# test-board-128-256.net
KiCad netlist of a schematic drawn in EAGLE
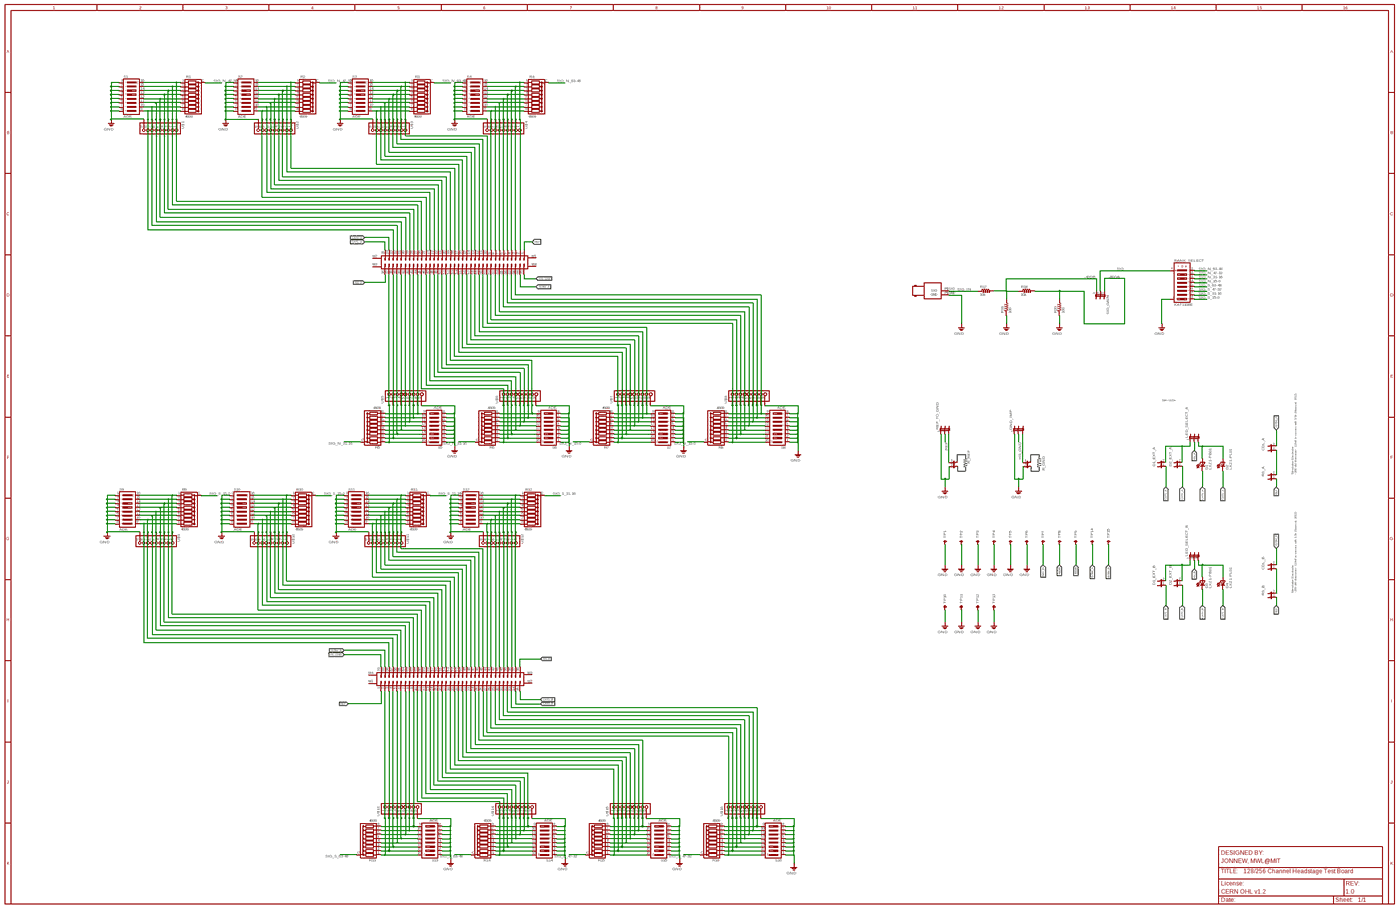
[diagram p0: schematic, sheet 1, overview]
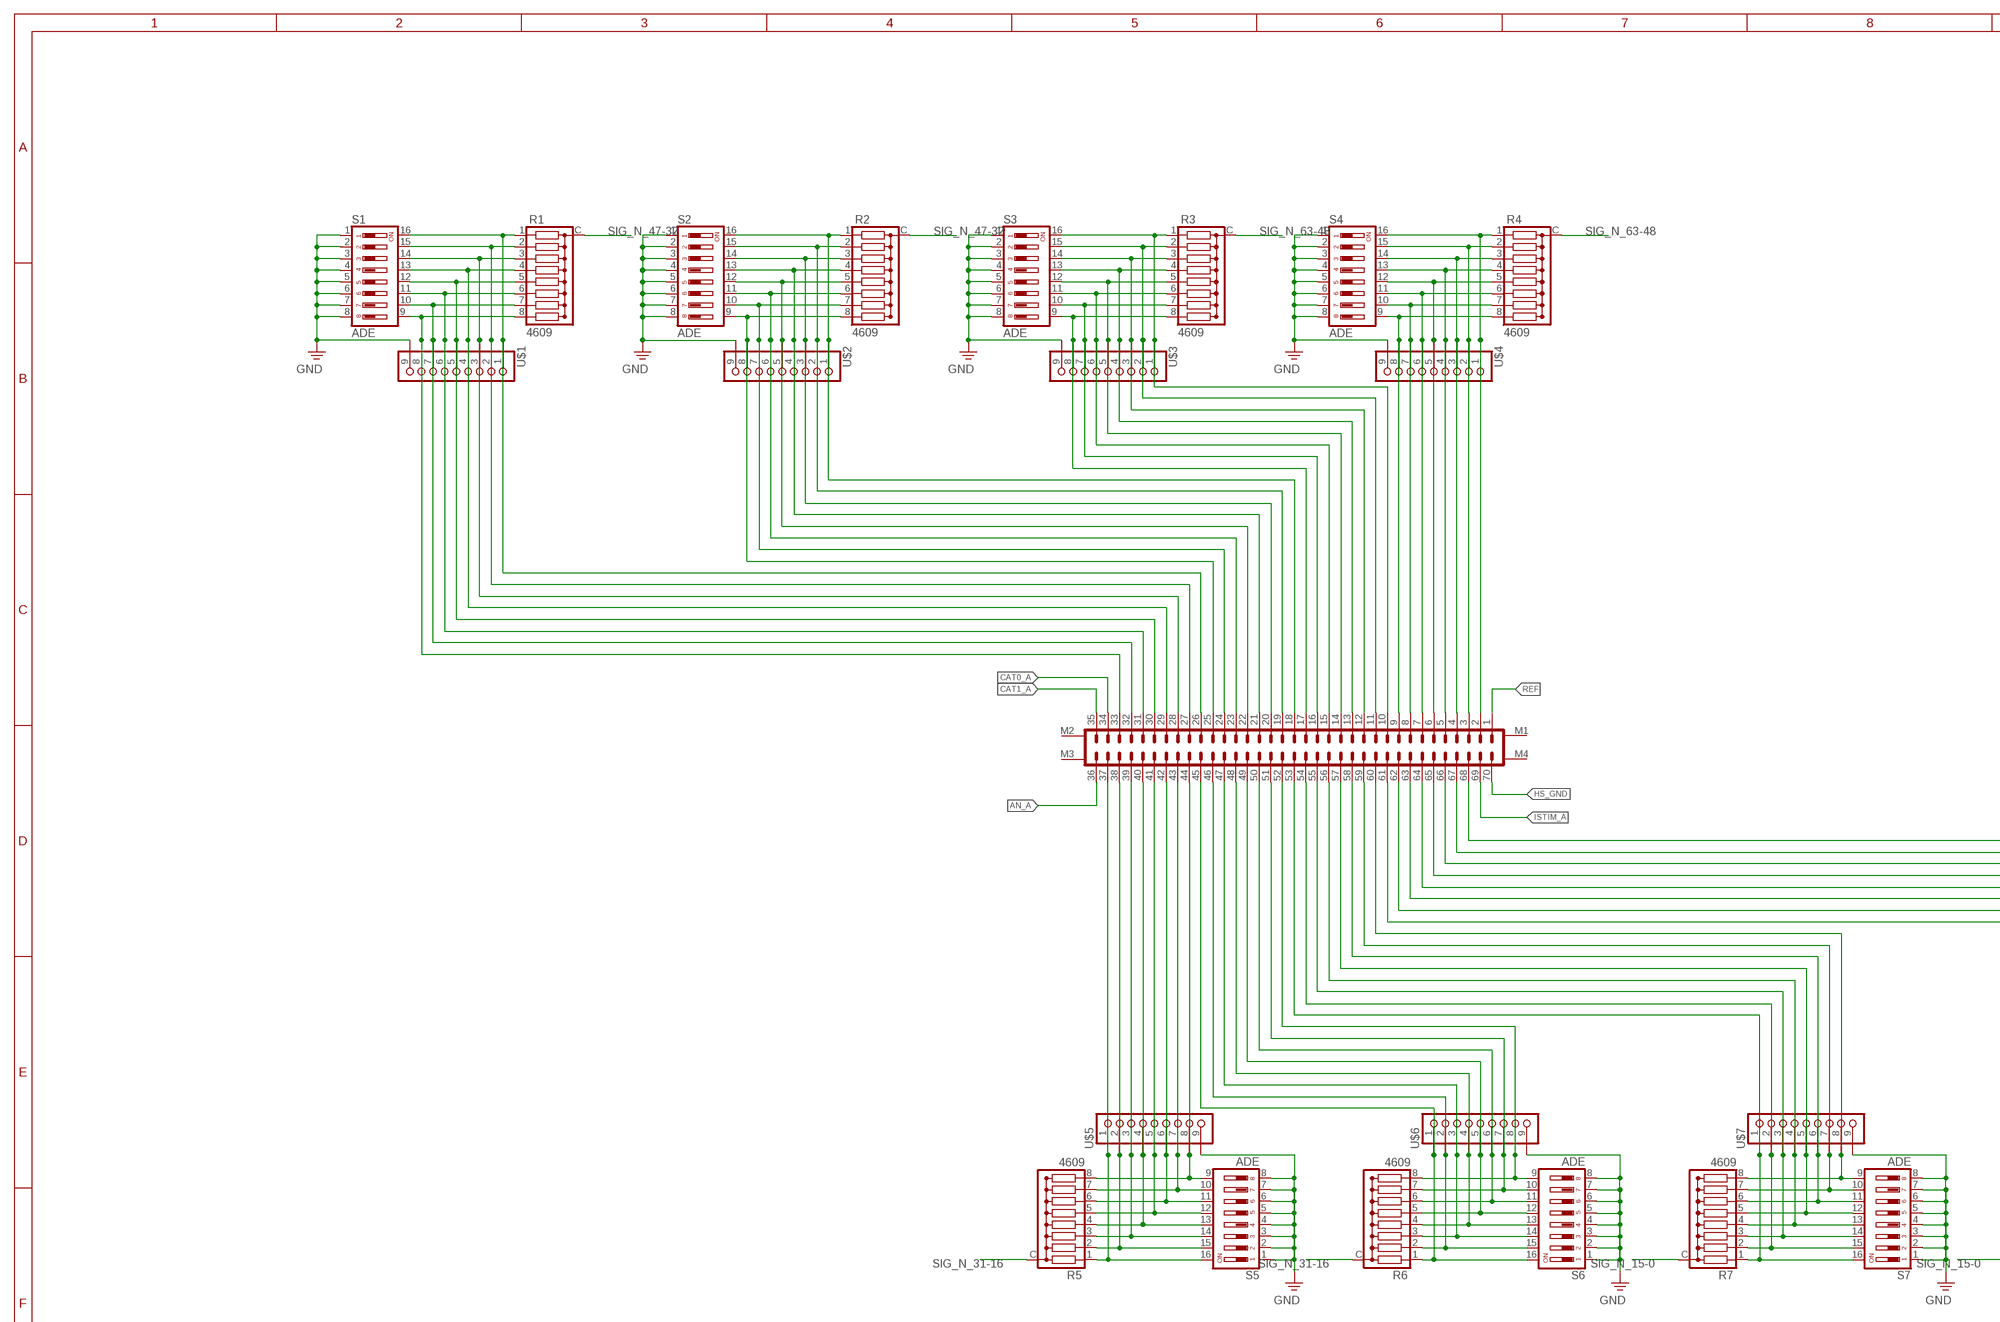
[diagram p1: schematic, sheet 1, part 1 of 4]
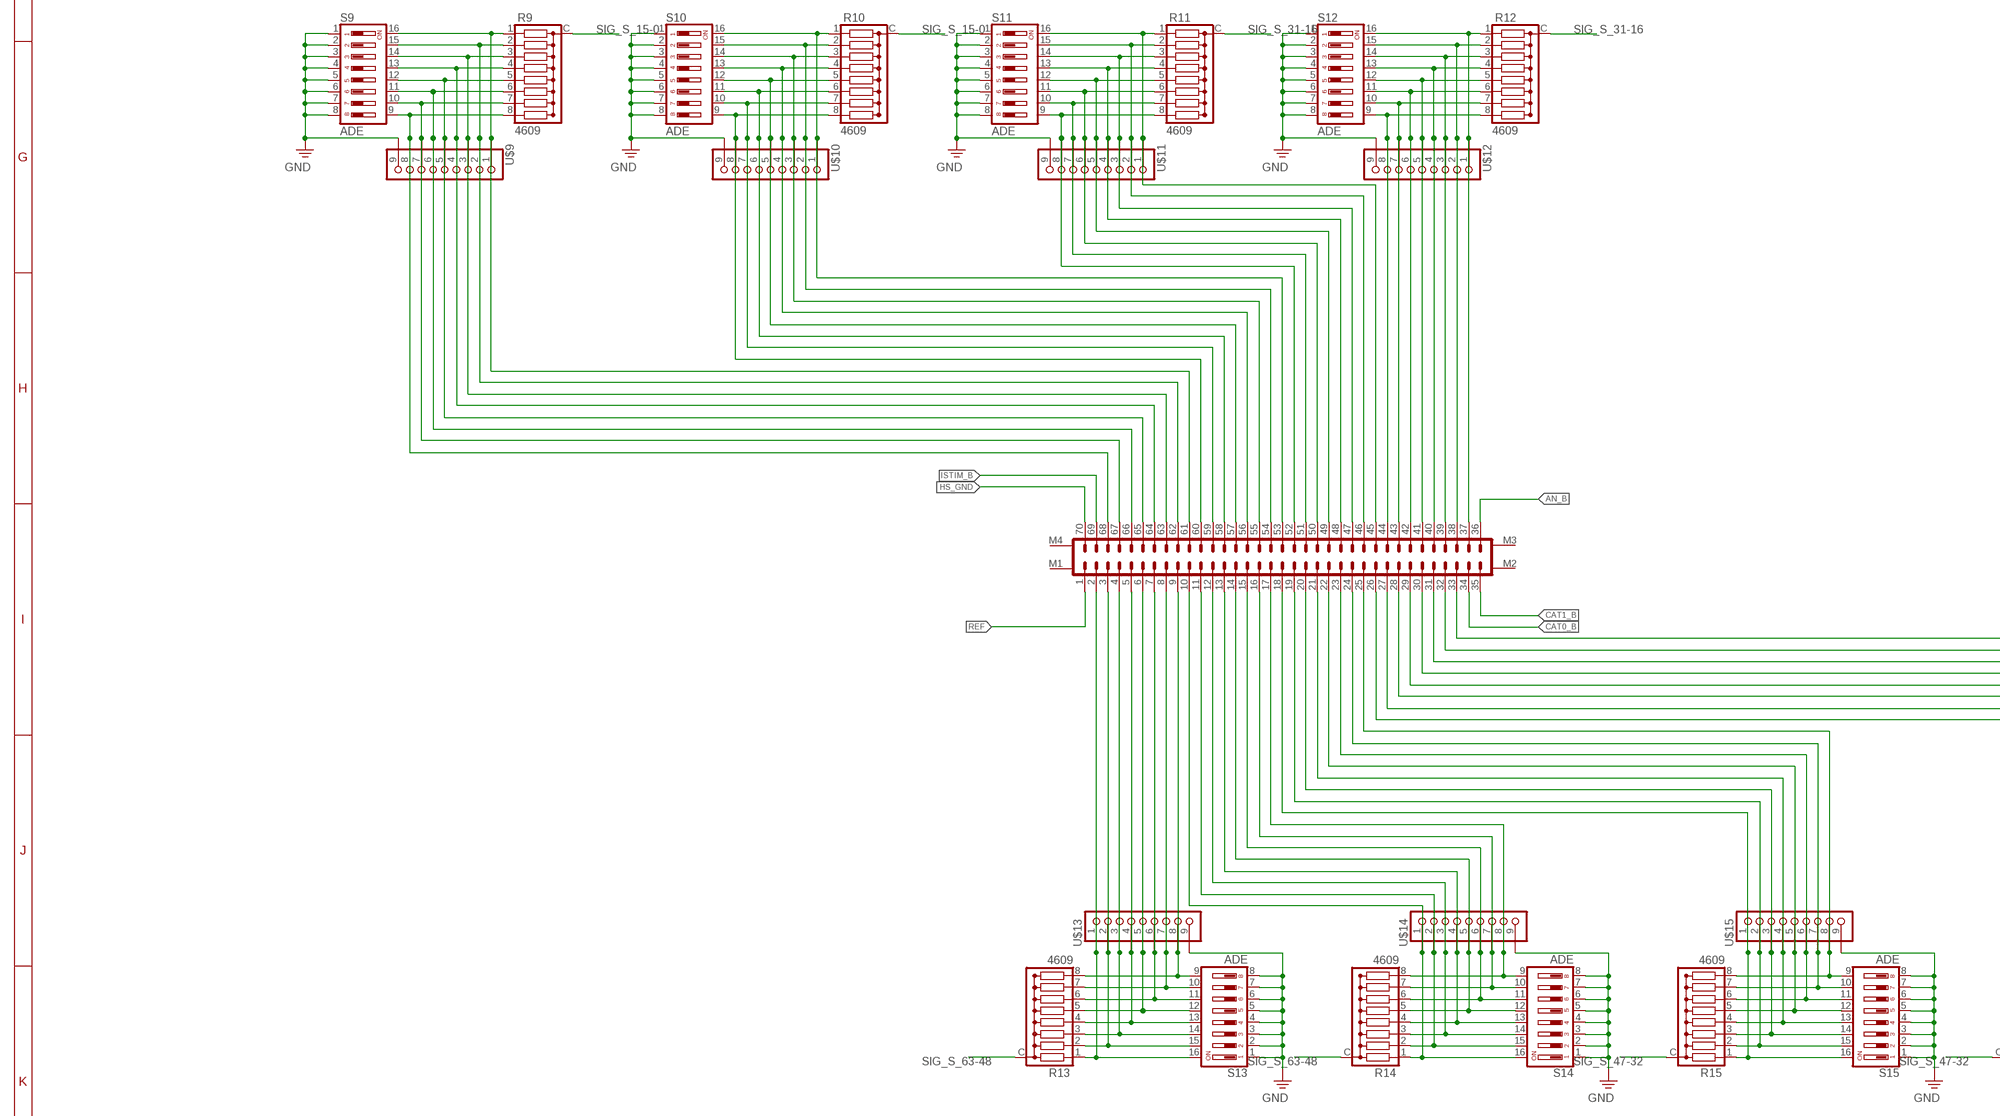
[diagram p2: schematic, sheet 1, part 2 of 4]
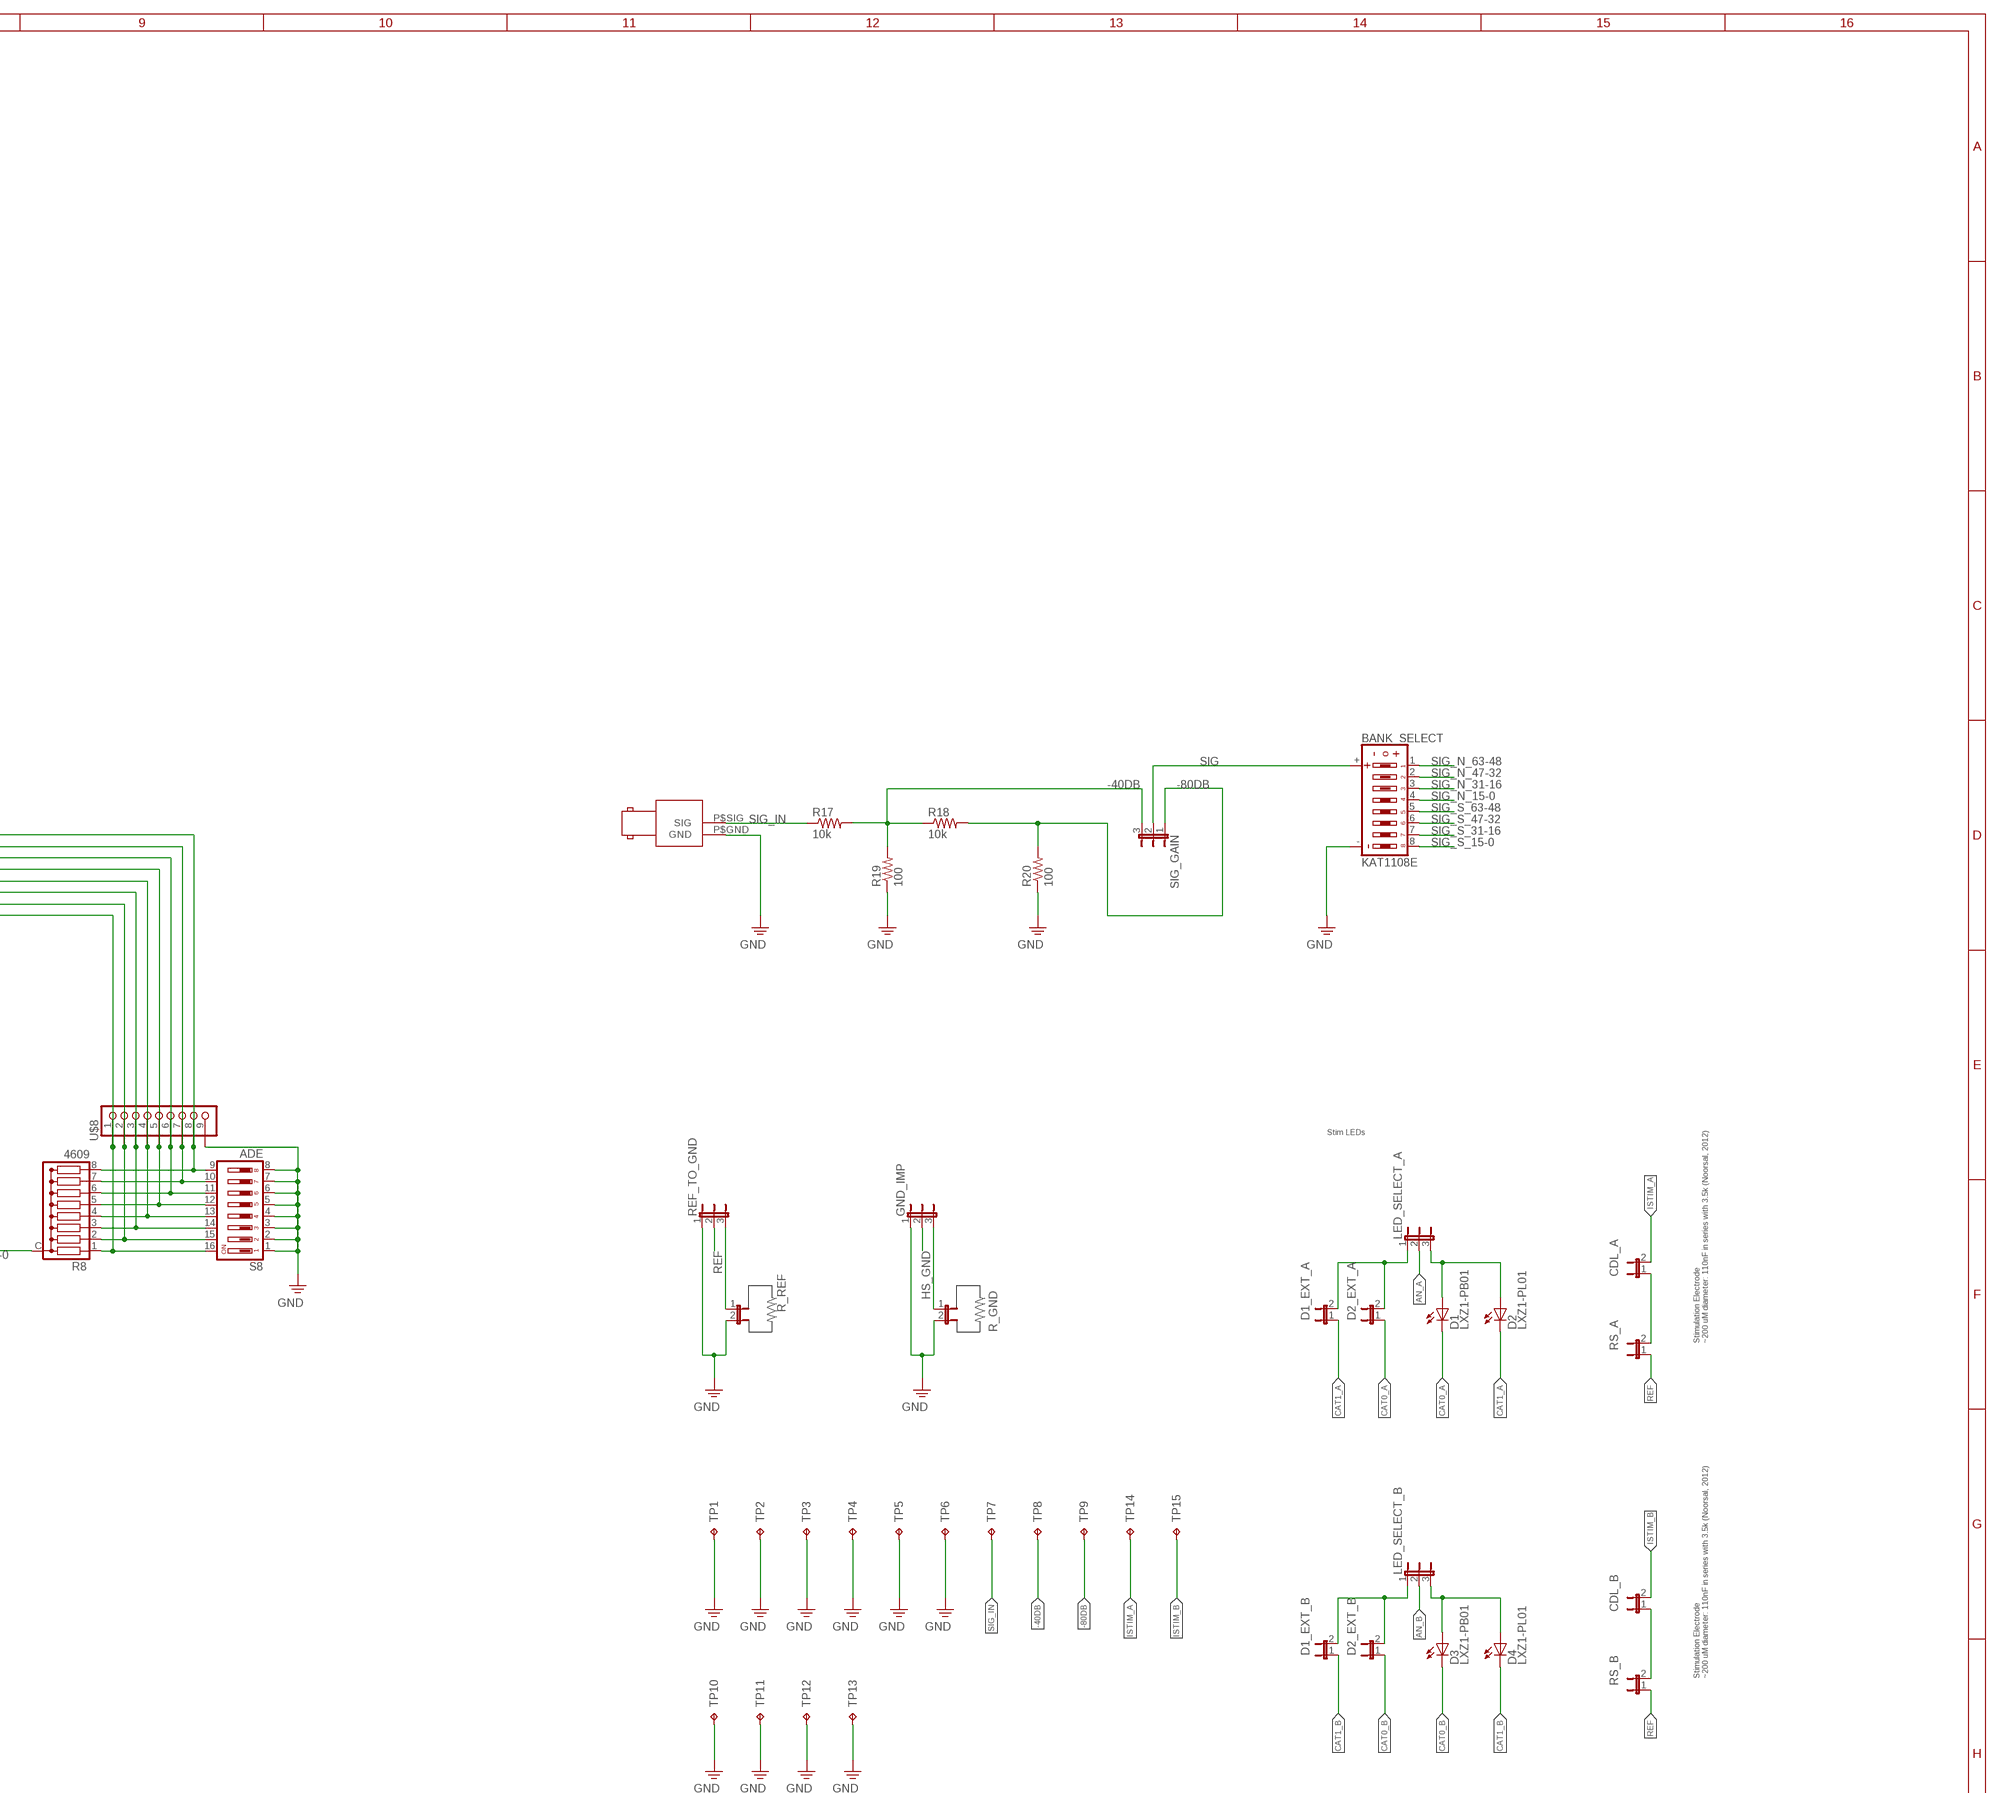
[diagram p3: schematic, sheet 1, part 3 of 4]
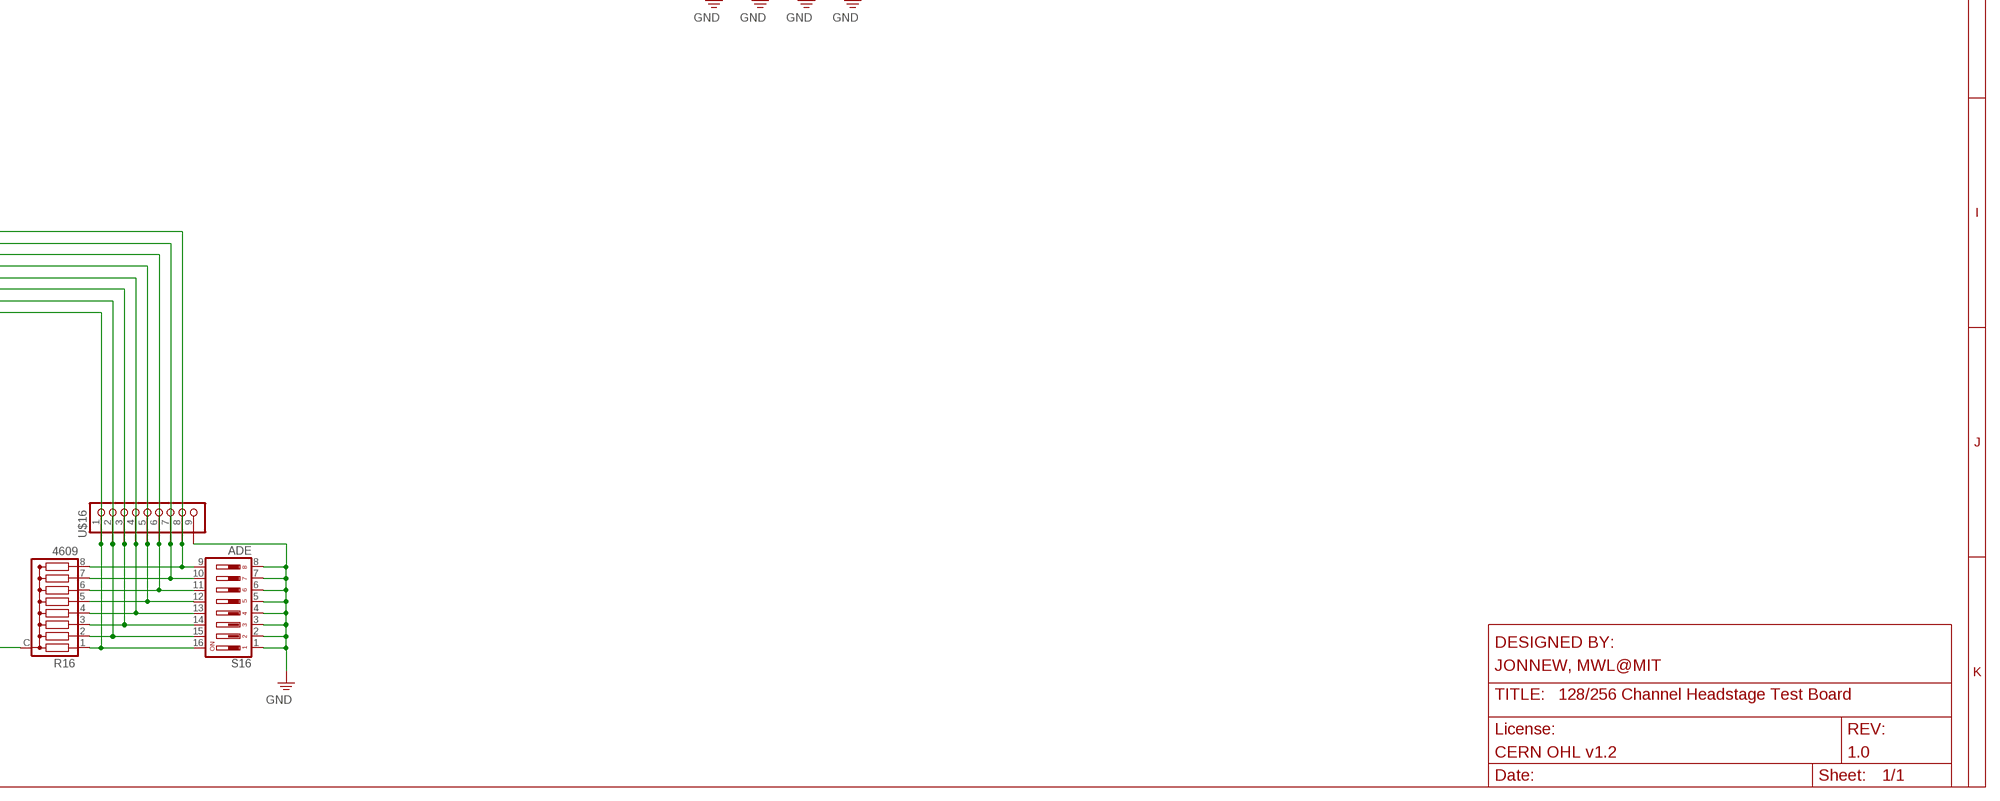
[diagram p4: schematic, sheet 1, part 4 of 4]

(export (version "E")
  (design (tool "Eeschema 10.0.6"))
  (components
    (comp (ref "A-OR-D")
      (value "DF40HEAD")
      (footprint "eagle-import:DF40-70HEAD")
      (libsource (lib "eagle-import") (part "PINHD-2X35+4_DF40-70HEAD"))
    )
    (comp (ref "B-OR-C")
      (value "DF40HEAD")
      (footprint "eagle-import:DF40-70HEAD")
      (libsource (lib "eagle-import") (part "PINHD-2X35+4_DF40-70HEAD"))
    )
    (comp (ref "BANK_SELECT")
      (value "KAT1108E")
      (footprint "eagle-import:206-124_DIP8-SPDT")
      (libsource (lib "eagle-import") (part "DIPSW-008-SPDT_206-124"))
    )
    (comp (ref "CDL_A")
      (value "JP2E_THRU-HOLE")
      (footprint "eagle-import:JP2")
      (libsource (lib "eagle-import") (part "JP2E_THRU-HOLE"))
    )
    (comp (ref "CDL_B")
      (value "JP2E_THRU-HOLE")
      (footprint "eagle-import:JP2")
      (libsource (lib "eagle-import") (part "JP2E_THRU-HOLE"))
    )
    (comp (ref "D1")
      (value "LXZ1-PB01")
      (footprint "eagle-import:LXZ1")
      (libsource (lib "eagle-import") (part "LED_LXZ1"))
    )
    (comp (ref "D1_EXT_A")
      (value "JP2E_THRU-HOLE")
      (footprint "eagle-import:JP2")
      (libsource (lib "eagle-import") (part "JP2E_THRU-HOLE"))
    )
    (comp (ref "D1_EXT_B")
      (value "JP2E_THRU-HOLE")
      (footprint "eagle-import:JP2")
      (libsource (lib "eagle-import") (part "JP2E_THRU-HOLE"))
    )
    (comp (ref "D2")
      (value "LXZ1-PL01")
      (footprint "eagle-import:LXZ1")
      (libsource (lib "eagle-import") (part "LED_LXZ1"))
    )
    (comp (ref "D2_EXT_A")
      (value "JP2E_THRU-HOLE")
      (footprint "eagle-import:JP2")
      (libsource (lib "eagle-import") (part "JP2E_THRU-HOLE"))
    )
    (comp (ref "D2_EXT_B")
      (value "JP2E_THRU-HOLE")
      (footprint "eagle-import:JP2")
      (libsource (lib "eagle-import") (part "JP2E_THRU-HOLE"))
    )
    (comp (ref "D3")
      (value "LXZ1-PB01")
      (footprint "eagle-import:LXZ1")
      (libsource (lib "eagle-import") (part "LED_LXZ1"))
    )
    (comp (ref "D4")
      (value "LXZ1-PL01")
      (footprint "eagle-import:LXZ1")
      (libsource (lib "eagle-import") (part "LED_LXZ1"))
    )
    (comp (ref "GND_IMP")
      (value "JP3E")
      (footprint "eagle-import:JP3")
      (libsource (lib "eagle-import") (part "JP3E"))
    )
    (comp (ref "LED_SELECT_A")
      (value "JP3E")
      (footprint "eagle-import:JP3")
      (libsource (lib "eagle-import") (part "JP3E"))
    )
    (comp (ref "LED_SELECT_B")
      (value "JP3E")
      (footprint "eagle-import:JP3")
      (libsource (lib "eagle-import") (part "JP3E"))
    )
    (comp (ref "R1")
      (value "4609")
      (footprint "eagle-import:RNX8-0.1")
      (libsource (lib "eagle-import") (part "RN1X8"))
    )
    (comp (ref "R2")
      (value "4609")
      (footprint "eagle-import:RNX8-0.1")
      (libsource (lib "eagle-import") (part "RN1X8"))
    )
    (comp (ref "R3")
      (value "4609")
      (footprint "eagle-import:RNX8-0.1")
      (libsource (lib "eagle-import") (part "RN1X8"))
    )
    (comp (ref "R4")
      (value "4609")
      (footprint "eagle-import:RNX8-0.1")
      (libsource (lib "eagle-import") (part "RN1X8"))
    )
    (comp (ref "R5")
      (value "4609")
      (footprint "eagle-import:RNX8-0.1")
      (libsource (lib "eagle-import") (part "RN1X8"))
    )
    (comp (ref "R6")
      (value "4609")
      (footprint "eagle-import:RNX8-0.1")
      (libsource (lib "eagle-import") (part "RN1X8"))
    )
    (comp (ref "R7")
      (value "4609")
      (footprint "eagle-import:RNX8-0.1")
      (libsource (lib "eagle-import") (part "RN1X8"))
    )
    (comp (ref "R8")
      (value "4609")
      (footprint "eagle-import:RNX8-0.1")
      (libsource (lib "eagle-import") (part "RN1X8"))
    )
    (comp (ref "R9")
      (value "4609")
      (footprint "eagle-import:RNX8-0.1")
      (libsource (lib "eagle-import") (part "RN1X8"))
    )
    (comp (ref "R10")
      (value "4609")
      (footprint "eagle-import:RNX8-0.1")
      (libsource (lib "eagle-import") (part "RN1X8"))
    )
    (comp (ref "R11")
      (value "4609")
      (footprint "eagle-import:RNX8-0.1")
      (libsource (lib "eagle-import") (part "RN1X8"))
    )
    (comp (ref "R12")
      (value "4609")
      (footprint "eagle-import:RNX8-0.1")
      (libsource (lib "eagle-import") (part "RN1X8"))
    )
    (comp (ref "R13")
      (value "4609")
      (footprint "eagle-import:RNX8-0.1")
      (libsource (lib "eagle-import") (part "RN1X8"))
    )
    (comp (ref "R14")
      (value "4609")
      (footprint "eagle-import:RNX8-0.1")
      (libsource (lib "eagle-import") (part "RN1X8"))
    )
    (comp (ref "R15")
      (value "4609")
      (footprint "eagle-import:RNX8-0.1")
      (libsource (lib "eagle-import") (part "RN1X8"))
    )
    (comp (ref "R16")
      (value "4609")
      (footprint "eagle-import:RNX8-0.1")
      (libsource (lib "eagle-import") (part "RN1X8"))
    )
    (comp (ref "R17")
      (value "10k")
      (footprint "eagle-import:0805")
      (libsource (lib "eagle-import") (part "R_0805"))
    )
    (comp (ref "R18")
      (value "10k")
      (footprint "eagle-import:0805")
      (libsource (lib "eagle-import") (part "R_0805"))
    )
    (comp (ref "R19")
      (value "100")
      (footprint "eagle-import:0805")
      (libsource (lib "eagle-import") (part "R_0805"))
    )
    (comp (ref "R20")
      (value "100")
      (footprint "eagle-import:0805")
      (libsource (lib "eagle-import") (part "R_0805"))
    )
    (comp (ref "REF_TO_GND")
      (value "JP3E")
      (footprint "eagle-import:JP3")
      (libsource (lib "eagle-import") (part "JP3E"))
    )
    (comp (ref "RS_A")
      (value "JP2E_THRU-HOLE")
      (footprint "eagle-import:JP2")
      (libsource (lib "eagle-import") (part "JP2E_THRU-HOLE"))
    )
    (comp (ref "RS_B")
      (value "JP2E_THRU-HOLE")
      (footprint "eagle-import:JP2")
      (libsource (lib "eagle-import") (part "JP2E_THRU-HOLE"))
    )
    (comp (ref "R_GND")
      (value "JP2E_THRU-HOLE")
      (footprint "eagle-import:JP2")
      (libsource (lib "eagle-import") (part "JP2E_THRU-HOLE"))
    )
    (comp (ref "R_REF")
      (value "JP2E_THRU-HOLE")
      (footprint "eagle-import:JP2")
      (libsource (lib "eagle-import") (part "JP2E_THRU-HOLE"))
    )
    (comp (ref "S1")
      (value "ADE")
      (footprint "eagle-import:ADE_DIP8-SPST")
      (libsource (lib "eagle-import") (part "DIPSW-008_ADE"))
    )
    (comp (ref "S2")
      (value "ADE")
      (footprint "eagle-import:ADE_DIP8-SPST")
      (libsource (lib "eagle-import") (part "DIPSW-008_ADE"))
    )
    (comp (ref "S3")
      (value "ADE")
      (footprint "eagle-import:ADE_DIP8-SPST")
      (libsource (lib "eagle-import") (part "DIPSW-008_ADE"))
    )
    (comp (ref "S4")
      (value "ADE")
      (footprint "eagle-import:ADE_DIP8-SPST")
      (libsource (lib "eagle-import") (part "DIPSW-008_ADE"))
    )
    (comp (ref "S5")
      (value "ADE")
      (footprint "eagle-import:ADE_DIP8-SPST")
      (libsource (lib "eagle-import") (part "DIPSW-008_ADE"))
    )
    (comp (ref "S6")
      (value "ADE")
      (footprint "eagle-import:ADE_DIP8-SPST")
      (libsource (lib "eagle-import") (part "DIPSW-008_ADE"))
    )
    (comp (ref "S7")
      (value "ADE")
      (footprint "eagle-import:ADE_DIP8-SPST")
      (libsource (lib "eagle-import") (part "DIPSW-008_ADE"))
    )
    (comp (ref "S8")
      (value "ADE")
      (footprint "eagle-import:ADE_DIP8-SPST")
      (libsource (lib "eagle-import") (part "DIPSW-008_ADE"))
    )
    (comp (ref "S9")
      (value "ADE")
      (footprint "eagle-import:ADE_DIP8-SPST")
      (libsource (lib "eagle-import") (part "DIPSW-008_ADE"))
    )
    (comp (ref "S10")
      (value "ADE")
      (footprint "eagle-import:ADE_DIP8-SPST")
      (libsource (lib "eagle-import") (part "DIPSW-008_ADE"))
    )
    (comp (ref "S11")
      (value "ADE")
      (footprint "eagle-import:ADE_DIP8-SPST")
      (libsource (lib "eagle-import") (part "DIPSW-008_ADE"))
    )
    (comp (ref "S12")
      (value "ADE")
      (footprint "eagle-import:ADE_DIP8-SPST")
      (libsource (lib "eagle-import") (part "DIPSW-008_ADE"))
    )
    (comp (ref "S13")
      (value "ADE")
      (footprint "eagle-import:ADE_DIP8-SPST")
      (libsource (lib "eagle-import") (part "DIPSW-008_ADE"))
    )
    (comp (ref "S14")
      (value "ADE")
      (footprint "eagle-import:ADE_DIP8-SPST")
      (libsource (lib "eagle-import") (part "DIPSW-008_ADE"))
    )
    (comp (ref "S15")
      (value "ADE")
      (footprint "eagle-import:ADE_DIP8-SPST")
      (libsource (lib "eagle-import") (part "DIPSW-008_ADE"))
    )
    (comp (ref "S16")
      (value "ADE")
      (footprint "eagle-import:ADE_DIP8-SPST")
      (libsource (lib "eagle-import") (part "DIPSW-008_ADE"))
    )
    (comp (ref "SIG_GAIN")
      (value "JP3E")
      (footprint "eagle-import:JP3")
      (libsource (lib "eagle-import") (part "JP3E"))
    )
    (comp (ref "SIG_IN")
      (value "1-1634622-0")
      (footprint "eagle-import:BNC_RIGHT_ANGLE")
      (libsource (lib "eagle-import") (part "BNC_RIGHT_ANGLE"))
    )
    (comp (ref "TP1")
      (value "GND")
      (footprint "eagle-import:P1-20")
      (libsource (lib "eagle-import") (part "TPPAD1-20"))
    )
    (comp (ref "TP2")
      (value "GND")
      (footprint "eagle-import:P1-20")
      (libsource (lib "eagle-import") (part "TPPAD1-20"))
    )
    (comp (ref "TP3")
      (value "GND")
      (footprint "eagle-import:P1-20")
      (libsource (lib "eagle-import") (part "TPPAD1-20"))
    )
    (comp (ref "TP4")
      (value "GND")
      (footprint "eagle-import:P1-20")
      (libsource (lib "eagle-import") (part "TPPAD1-20"))
    )
    (comp (ref "TP5")
      (value "GND")
      (footprint "eagle-import:P1-20")
      (libsource (lib "eagle-import") (part "TPPAD1-20"))
    )
    (comp (ref "TP6")
      (value "GND")
      (footprint "eagle-import:P1-20")
      (libsource (lib "eagle-import") (part "TPPAD1-20"))
    )
    (comp (ref "TP7")
      (value "SIG_IN")
      (footprint "eagle-import:P1-20")
      (libsource (lib "eagle-import") (part "TPPAD1-20"))
    )
    (comp (ref "TP8")
      (value "-40dB")
      (footprint "eagle-import:P1-20")
      (libsource (lib "eagle-import") (part "TPPAD1-20"))
    )
    (comp (ref "TP9")
      (value "-80dB")
      (footprint "eagle-import:P1-20")
      (libsource (lib "eagle-import") (part "TPPAD1-20"))
    )
    (comp (ref "TP10")
      (value "TP_4-40")
      (footprint "eagle-import:4-40_PLATED")
      (libsource (lib "eagle-import") (part "TP_4-40"))
    )
    (comp (ref "TP11")
      (value "TP_4-40")
      (footprint "eagle-import:4-40_PLATED")
      (libsource (lib "eagle-import") (part "TP_4-40"))
    )
    (comp (ref "TP12")
      (value "TP_4-40")
      (footprint "eagle-import:4-40_PLATED")
      (libsource (lib "eagle-import") (part "TP_4-40"))
    )
    (comp (ref "TP13")
      (value "TP_4-40")
      (footprint "eagle-import:4-40_PLATED")
      (libsource (lib "eagle-import") (part "TP_4-40"))
    )
    (comp (ref "TP14")
      (value "V_ISTIM_A")
      (footprint "eagle-import:P1-20")
      (libsource (lib "eagle-import") (part "TPPAD1-20"))
    )
    (comp (ref "TP15")
      (value "V_ISTIM_B")
      (footprint "eagle-import:P1-20")
      (libsource (lib "eagle-import") (part "TPPAD1-20"))
    )
    (comp (ref "U$1")
      (value "PINHD-1X9")
      (footprint "eagle-import:1X09")
      (libsource (lib "eagle-import") (part "PINHD-1X9"))
    )
    (comp (ref "U$2")
      (value "PINHD-1X9")
      (footprint "eagle-import:1X09")
      (libsource (lib "eagle-import") (part "PINHD-1X9"))
    )
    (comp (ref "U$3")
      (value "PINHD-1X9")
      (footprint "eagle-import:1X09")
      (libsource (lib "eagle-import") (part "PINHD-1X9"))
    )
    (comp (ref "U$4")
      (value "PINHD-1X9")
      (footprint "eagle-import:1X09")
      (libsource (lib "eagle-import") (part "PINHD-1X9"))
    )
    (comp (ref "U$5")
      (value "PINHD-1X9")
      (footprint "eagle-import:1X09")
      (libsource (lib "eagle-import") (part "PINHD-1X9"))
    )
    (comp (ref "U$6")
      (value "PINHD-1X9")
      (footprint "eagle-import:1X09")
      (libsource (lib "eagle-import") (part "PINHD-1X9"))
    )
    (comp (ref "U$7")
      (value "PINHD-1X9")
      (footprint "eagle-import:1X09")
      (libsource (lib "eagle-import") (part "PINHD-1X9"))
    )
    (comp (ref "U$8")
      (value "PINHD-1X9")
      (footprint "eagle-import:1X09")
      (libsource (lib "eagle-import") (part "PINHD-1X9"))
    )
    (comp (ref "U$9")
      (value "PINHD-1X9")
      (footprint "eagle-import:1X09")
      (libsource (lib "eagle-import") (part "PINHD-1X9"))
    )
    (comp (ref "U$10")
      (value "PINHD-1X9")
      (footprint "eagle-import:1X09")
      (libsource (lib "eagle-import") (part "PINHD-1X9"))
    )
    (comp (ref "U$11")
      (value "PINHD-1X9")
      (footprint "eagle-import:1X09")
      (libsource (lib "eagle-import") (part "PINHD-1X9"))
    )
    (comp (ref "U$12")
      (value "PINHD-1X9")
      (footprint "eagle-import:1X09")
      (libsource (lib "eagle-import") (part "PINHD-1X9"))
    )
    (comp (ref "U$13")
      (value "PINHD-1X9")
      (footprint "eagle-import:1X09")
      (libsource (lib "eagle-import") (part "PINHD-1X9"))
    )
    (comp (ref "U$14")
      (value "PINHD-1X9")
      (footprint "eagle-import:1X09")
      (libsource (lib "eagle-import") (part "PINHD-1X9"))
    )
    (comp (ref "U$15")
      (value "PINHD-1X9")
      (footprint "eagle-import:1X09")
      (libsource (lib "eagle-import") (part "PINHD-1X9"))
    )
    (comp (ref "U$16")
      (value "PINHD-1X9")
      (footprint "eagle-import:1X09")
      (libsource (lib "eagle-import") (part "PINHD-1X9"))
    )
  )
  (nets
    (net (code "1") (name "-40DB") (class "Default")
      (node (ref "R17") (pin "2") (pinfunction "2_2") (pintype "passive"))
      (node (ref "R18") (pin "1") (pinfunction "1_1") (pintype "passive"))
      (node (ref "R19") (pin "2") (pinfunction "2_2") (pintype "passive"))
      (node (ref "SIG_GAIN") (pin "3") (pinfunction "3_3") (pintype "passive"))
      (node (ref "TP8") (pin "TP") (pinfunction "TP_TP") (pintype "input"))
    )
    (net (code "2") (name "-80DB") (class "Default")
      (node (ref "R18") (pin "2") (pinfunction "2_2") (pintype "passive"))
      (node (ref "R20") (pin "2") (pinfunction "2_2") (pintype "passive"))
      (node (ref "SIG_GAIN") (pin "1") (pinfunction "1_1") (pintype "passive"))
      (node (ref "TP9") (pin "TP") (pinfunction "TP_TP") (pintype "input"))
    )
    (net (code "3") (name "/SIG") (class "Default")
      (node (ref "BANK_SELECT") (pin "+") (pinfunction "+_+") (pintype "passive"))
      (node (ref "SIG_GAIN") (pin "2") (pinfunction "2_2") (pintype "passive"))
    )
    (net (code "4") (name "/SIG_N_15-0") (class "Default")
      (node (ref "BANK_SELECT") (pin "4") (pinfunction "4_4") (pintype "passive"))
      (node (ref "R7") (pin "C") (pinfunction "C_C") (pintype "passive"))
      (node (ref "R8") (pin "C") (pinfunction "C_C") (pintype "passive"))
    )
    (net (code "5") (name "/SIG_N_31-16") (class "Default")
      (node (ref "BANK_SELECT") (pin "3") (pinfunction "3_3") (pintype "passive"))
      (node (ref "R5") (pin "C") (pinfunction "C_C") (pintype "passive"))
      (node (ref "R6") (pin "C") (pinfunction "C_C") (pintype "passive"))
    )
    (net (code "6") (name "/SIG_N_47-32") (class "Default")
      (node (ref "BANK_SELECT") (pin "2") (pinfunction "2_2") (pintype "passive"))
      (node (ref "R1") (pin "C") (pinfunction "C_C") (pintype "passive"))
      (node (ref "R2") (pin "C") (pinfunction "C_C") (pintype "passive"))
    )
    (net (code "7") (name "/SIG_N_63-48") (class "Default")
      (node (ref "BANK_SELECT") (pin "1") (pinfunction "1_1") (pintype "passive"))
      (node (ref "R3") (pin "C") (pinfunction "C_C") (pintype "passive"))
      (node (ref "R4") (pin "C") (pinfunction "C_C") (pintype "passive"))
    )
    (net (code "8") (name "/SIG_S_15-0") (class "Default")
      (node (ref "BANK_SELECT") (pin "8") (pinfunction "8_8") (pintype "passive"))
      (node (ref "R10") (pin "C") (pinfunction "C_C") (pintype "passive"))
      (node (ref "R9") (pin "C") (pinfunction "C_C") (pintype "passive"))
    )
    (net (code "9") (name "/SIG_S_31-16") (class "Default")
      (node (ref "BANK_SELECT") (pin "7") (pinfunction "7_7") (pintype "passive"))
      (node (ref "R11") (pin "C") (pinfunction "C_C") (pintype "passive"))
      (node (ref "R12") (pin "C") (pinfunction "C_C") (pintype "passive"))
    )
    (net (code "10") (name "/SIG_S_47-32") (class "Default")
      (node (ref "BANK_SELECT") (pin "6") (pinfunction "6_6") (pintype "passive"))
      (node (ref "R15") (pin "C") (pinfunction "C_C") (pintype "passive"))
      (node (ref "R16") (pin "C") (pinfunction "C_C") (pintype "passive"))
    )
    (net (code "11") (name "/SIG_S_63-48") (class "Default")
      (node (ref "BANK_SELECT") (pin "5") (pinfunction "5_5") (pintype "passive"))
      (node (ref "R13") (pin "C") (pinfunction "C_C") (pintype "passive"))
      (node (ref "R14") (pin "C") (pinfunction "C_C") (pintype "passive"))
    )
    (net (code "12") (name "AN_A") (class "Default")
      (node (ref "A-OR-D") (pin "36") (pinfunction "36_36") (pintype "bidirectional"))
      (node (ref "LED_SELECT_A") (pin "2") (pinfunction "2_2") (pintype "passive"))
    )
    (net (code "13") (name "AN_B") (class "Default")
      (node (ref "B-OR-C") (pin "36") (pinfunction "36_36") (pintype "bidirectional"))
      (node (ref "LED_SELECT_B") (pin "2") (pinfunction "2_2") (pintype "passive"))
    )
    (net (code "14") (name "CAT0_A") (class "Default")
      (node (ref "A-OR-D") (pin "34") (pinfunction "34_34") (pintype "bidirectional"))
      (node (ref "D1") (pin "C") (pinfunction "C_C") (pintype "passive"))
      (node (ref "D2_EXT_A") (pin "1") (pinfunction "1_1") (pintype "passive"))
    )
    (net (code "15") (name "CAT0_B") (class "Default")
      (node (ref "B-OR-C") (pin "34") (pinfunction "34_34") (pintype "bidirectional"))
      (node (ref "D2_EXT_B") (pin "1") (pinfunction "1_1") (pintype "passive"))
      (node (ref "D3") (pin "C") (pinfunction "C_C") (pintype "passive"))
    )
    (net (code "16") (name "CAT1_A") (class "Default")
      (node (ref "A-OR-D") (pin "35") (pinfunction "35_35") (pintype "bidirectional"))
      (node (ref "D1_EXT_A") (pin "1") (pinfunction "1_1") (pintype "passive"))
      (node (ref "D2") (pin "C") (pinfunction "C_C") (pintype "passive"))
    )
    (net (code "17") (name "CAT1_B") (class "Default")
      (node (ref "B-OR-C") (pin "35") (pinfunction "35_35") (pintype "bidirectional"))
      (node (ref "D1_EXT_B") (pin "1") (pinfunction "1_1") (pintype "passive"))
      (node (ref "D4") (pin "C") (pinfunction "C_C") (pintype "passive"))
    )
    (net (code "18") (name "GND") (class "Default")
      (node (ref "BANK_SELECT") (pin "-") (pinfunction "-_-") (pintype "passive"))
      (node (ref "GND_IMP") (pin "1") (pinfunction "1_1") (pintype "passive"))
      (node (ref "R19") (pin "1") (pinfunction "1_1") (pintype "passive"))
      (node (ref "R20") (pin "1") (pinfunction "1_1") (pintype "passive"))
      (node (ref "REF_TO_GND") (pin "1") (pinfunction "1_1") (pintype "passive"))
      (node (ref "R_GND") (pin "2") (pinfunction "2_2") (pintype "passive"))
      (node (ref "R_REF") (pin "2") (pinfunction "2_2") (pintype "passive"))
      (node (ref "S1") (pin "1") (pinfunction "1_1") (pintype "passive"))
      (node (ref "S1") (pin "2") (pinfunction "2_2") (pintype "passive"))
      (node (ref "S1") (pin "3") (pinfunction "3_3") (pintype "passive"))
      (node (ref "S1") (pin "4") (pinfunction "4_4") (pintype "passive"))
      (node (ref "S1") (pin "5") (pinfunction "5_5") (pintype "passive"))
      (node (ref "S1") (pin "6") (pinfunction "6_6") (pintype "passive"))
      (node (ref "S1") (pin "7") (pinfunction "7_7") (pintype "passive"))
      (node (ref "S1") (pin "8") (pinfunction "8_8") (pintype "passive"))
      (node (ref "S10") (pin "1") (pinfunction "1_1") (pintype "passive"))
      (node (ref "S10") (pin "2") (pinfunction "2_2") (pintype "passive"))
      (node (ref "S10") (pin "3") (pinfunction "3_3") (pintype "passive"))
      (node (ref "S10") (pin "4") (pinfunction "4_4") (pintype "passive"))
      (node (ref "S10") (pin "5") (pinfunction "5_5") (pintype "passive"))
      (node (ref "S10") (pin "6") (pinfunction "6_6") (pintype "passive"))
      (node (ref "S10") (pin "7") (pinfunction "7_7") (pintype "passive"))
      (node (ref "S10") (pin "8") (pinfunction "8_8") (pintype "passive"))
      (node (ref "S11") (pin "1") (pinfunction "1_1") (pintype "passive"))
      (node (ref "S11") (pin "2") (pinfunction "2_2") (pintype "passive"))
      (node (ref "S11") (pin "3") (pinfunction "3_3") (pintype "passive"))
      (node (ref "S11") (pin "4") (pinfunction "4_4") (pintype "passive"))
      (node (ref "S11") (pin "5") (pinfunction "5_5") (pintype "passive"))
      (node (ref "S11") (pin "6") (pinfunction "6_6") (pintype "passive"))
      (node (ref "S11") (pin "7") (pinfunction "7_7") (pintype "passive"))
      (node (ref "S11") (pin "8") (pinfunction "8_8") (pintype "passive"))
      (node (ref "S12") (pin "1") (pinfunction "1_1") (pintype "passive"))
      (node (ref "S12") (pin "2") (pinfunction "2_2") (pintype "passive"))
      (node (ref "S12") (pin "3") (pinfunction "3_3") (pintype "passive"))
      (node (ref "S12") (pin "4") (pinfunction "4_4") (pintype "passive"))
      (node (ref "S12") (pin "5") (pinfunction "5_5") (pintype "passive"))
      (node (ref "S12") (pin "6") (pinfunction "6_6") (pintype "passive"))
      (node (ref "S12") (pin "7") (pinfunction "7_7") (pintype "passive"))
      (node (ref "S12") (pin "8") (pinfunction "8_8") (pintype "passive"))
      (node (ref "S13") (pin "1") (pinfunction "1_1") (pintype "passive"))
      (node (ref "S13") (pin "2") (pinfunction "2_2") (pintype "passive"))
      (node (ref "S13") (pin "3") (pinfunction "3_3") (pintype "passive"))
      (node (ref "S13") (pin "4") (pinfunction "4_4") (pintype "passive"))
      (node (ref "S13") (pin "5") (pinfunction "5_5") (pintype "passive"))
      (node (ref "S13") (pin "6") (pinfunction "6_6") (pintype "passive"))
      (node (ref "S13") (pin "7") (pinfunction "7_7") (pintype "passive"))
      (node (ref "S13") (pin "8") (pinfunction "8_8") (pintype "passive"))
      (node (ref "S14") (pin "1") (pinfunction "1_1") (pintype "passive"))
      (node (ref "S14") (pin "2") (pinfunction "2_2") (pintype "passive"))
      (node (ref "S14") (pin "3") (pinfunction "3_3") (pintype "passive"))
      (node (ref "S14") (pin "4") (pinfunction "4_4") (pintype "passive"))
      (node (ref "S14") (pin "5") (pinfunction "5_5") (pintype "passive"))
      (node (ref "S14") (pin "6") (pinfunction "6_6") (pintype "passive"))
      (node (ref "S14") (pin "7") (pinfunction "7_7") (pintype "passive"))
      (node (ref "S14") (pin "8") (pinfunction "8_8") (pintype "passive"))
      (node (ref "S15") (pin "1") (pinfunction "1_1") (pintype "passive"))
      (node (ref "S15") (pin "2") (pinfunction "2_2") (pintype "passive"))
      (node (ref "S15") (pin "3") (pinfunction "3_3") (pintype "passive"))
      (node (ref "S15") (pin "4") (pinfunction "4_4") (pintype "passive"))
      (node (ref "S15") (pin "5") (pinfunction "5_5") (pintype "passive"))
      (node (ref "S15") (pin "6") (pinfunction "6_6") (pintype "passive"))
      (node (ref "S15") (pin "7") (pinfunction "7_7") (pintype "passive"))
      (node (ref "S15") (pin "8") (pinfunction "8_8") (pintype "passive"))
      (node (ref "S16") (pin "1") (pinfunction "1_1") (pintype "passive"))
      (node (ref "S16") (pin "2") (pinfunction "2_2") (pintype "passive"))
      (node (ref "S16") (pin "3") (pinfunction "3_3") (pintype "passive"))
      (node (ref "S16") (pin "4") (pinfunction "4_4") (pintype "passive"))
      (node (ref "S16") (pin "5") (pinfunction "5_5") (pintype "passive"))
      (node (ref "S16") (pin "6") (pinfunction "6_6") (pintype "passive"))
      (node (ref "S16") (pin "7") (pinfunction "7_7") (pintype "passive"))
      (node (ref "S16") (pin "8") (pinfunction "8_8") (pintype "passive"))
      (node (ref "S2") (pin "1") (pinfunction "1_1") (pintype "passive"))
      (node (ref "S2") (pin "2") (pinfunction "2_2") (pintype "passive"))
      (node (ref "S2") (pin "3") (pinfunction "3_3") (pintype "passive"))
      (node (ref "S2") (pin "4") (pinfunction "4_4") (pintype "passive"))
      (node (ref "S2") (pin "5") (pinfunction "5_5") (pintype "passive"))
      (node (ref "S2") (pin "6") (pinfunction "6_6") (pintype "passive"))
      (node (ref "S2") (pin "7") (pinfunction "7_7") (pintype "passive"))
      (node (ref "S2") (pin "8") (pinfunction "8_8") (pintype "passive"))
      (node (ref "S3") (pin "1") (pinfunction "1_1") (pintype "passive"))
      (node (ref "S3") (pin "2") (pinfunction "2_2") (pintype "passive"))
      (node (ref "S3") (pin "3") (pinfunction "3_3") (pintype "passive"))
      (node (ref "S3") (pin "4") (pinfunction "4_4") (pintype "passive"))
      (node (ref "S3") (pin "5") (pinfunction "5_5") (pintype "passive"))
      (node (ref "S3") (pin "6") (pinfunction "6_6") (pintype "passive"))
      (node (ref "S3") (pin "7") (pinfunction "7_7") (pintype "passive"))
      (node (ref "S3") (pin "8") (pinfunction "8_8") (pintype "passive"))
      (node (ref "S4") (pin "1") (pinfunction "1_1") (pintype "passive"))
      (node (ref "S4") (pin "2") (pinfunction "2_2") (pintype "passive"))
      (node (ref "S4") (pin "3") (pinfunction "3_3") (pintype "passive"))
      (node (ref "S4") (pin "4") (pinfunction "4_4") (pintype "passive"))
      (node (ref "S4") (pin "5") (pinfunction "5_5") (pintype "passive"))
      (node (ref "S4") (pin "6") (pinfunction "6_6") (pintype "passive"))
      (node (ref "S4") (pin "7") (pinfunction "7_7") (pintype "passive"))
      (node (ref "S4") (pin "8") (pinfunction "8_8") (pintype "passive"))
      (node (ref "S5") (pin "1") (pinfunction "1_1") (pintype "passive"))
      (node (ref "S5") (pin "2") (pinfunction "2_2") (pintype "passive"))
      (node (ref "S5") (pin "3") (pinfunction "3_3") (pintype "passive"))
      (node (ref "S5") (pin "4") (pinfunction "4_4") (pintype "passive"))
      (node (ref "S5") (pin "5") (pinfunction "5_5") (pintype "passive"))
      (node (ref "S5") (pin "6") (pinfunction "6_6") (pintype "passive"))
      (node (ref "S5") (pin "7") (pinfunction "7_7") (pintype "passive"))
      (node (ref "S5") (pin "8") (pinfunction "8_8") (pintype "passive"))
      (node (ref "S6") (pin "1") (pinfunction "1_1") (pintype "passive"))
      (node (ref "S6") (pin "2") (pinfunction "2_2") (pintype "passive"))
      (node (ref "S6") (pin "3") (pinfunction "3_3") (pintype "passive"))
      (node (ref "S6") (pin "4") (pinfunction "4_4") (pintype "passive"))
      (node (ref "S6") (pin "5") (pinfunction "5_5") (pintype "passive"))
      (node (ref "S6") (pin "6") (pinfunction "6_6") (pintype "passive"))
      (node (ref "S6") (pin "7") (pinfunction "7_7") (pintype "passive"))
      (node (ref "S6") (pin "8") (pinfunction "8_8") (pintype "passive"))
      (node (ref "S7") (pin "1") (pinfunction "1_1") (pintype "passive"))
      (node (ref "S7") (pin "2") (pinfunction "2_2") (pintype "passive"))
      (node (ref "S7") (pin "3") (pinfunction "3_3") (pintype "passive"))
      (node (ref "S7") (pin "4") (pinfunction "4_4") (pintype "passive"))
      (node (ref "S7") (pin "5") (pinfunction "5_5") (pintype "passive"))
      (node (ref "S7") (pin "6") (pinfunction "6_6") (pintype "passive"))
      (node (ref "S7") (pin "7") (pinfunction "7_7") (pintype "passive"))
      (node (ref "S7") (pin "8") (pinfunction "8_8") (pintype "passive"))
      (node (ref "S8") (pin "1") (pinfunction "1_1") (pintype "passive"))
      (node (ref "S8") (pin "2") (pinfunction "2_2") (pintype "passive"))
      (node (ref "S8") (pin "3") (pinfunction "3_3") (pintype "passive"))
      (node (ref "S8") (pin "4") (pinfunction "4_4") (pintype "passive"))
      (node (ref "S8") (pin "5") (pinfunction "5_5") (pintype "passive"))
      (node (ref "S8") (pin "6") (pinfunction "6_6") (pintype "passive"))
      (node (ref "S8") (pin "7") (pinfunction "7_7") (pintype "passive"))
      (node (ref "S8") (pin "8") (pinfunction "8_8") (pintype "passive"))
      (node (ref "S9") (pin "1") (pinfunction "1_1") (pintype "passive"))
      (node (ref "S9") (pin "2") (pinfunction "2_2") (pintype "passive"))
      (node (ref "S9") (pin "3") (pinfunction "3_3") (pintype "passive"))
      (node (ref "S9") (pin "4") (pinfunction "4_4") (pintype "passive"))
      (node (ref "S9") (pin "5") (pinfunction "5_5") (pintype "passive"))
      (node (ref "S9") (pin "6") (pinfunction "6_6") (pintype "passive"))
      (node (ref "S9") (pin "7") (pinfunction "7_7") (pintype "passive"))
      (node (ref "S9") (pin "8") (pinfunction "8_8") (pintype "passive"))
      (node (ref "SIG_IN") (pin "P$GND") (pinfunction "GND_P$GND") (pintype "bidirectional"))
      (node (ref "TP1") (pin "TP") (pinfunction "TP_TP") (pintype "input"))
      (node (ref "TP10") (pin "P$1") (pinfunction "TP_P$1") (pintype "input"))
      (node (ref "TP11") (pin "P$1") (pinfunction "TP_P$1") (pintype "input"))
      (node (ref "TP12") (pin "P$1") (pinfunction "TP_P$1") (pintype "input"))
      (node (ref "TP13") (pin "P$1") (pinfunction "TP_P$1") (pintype "input"))
      (node (ref "TP2") (pin "TP") (pinfunction "TP_TP") (pintype "input"))
      (node (ref "TP3") (pin "TP") (pinfunction "TP_TP") (pintype "input"))
      (node (ref "TP4") (pin "TP") (pinfunction "TP_TP") (pintype "input"))
      (node (ref "TP5") (pin "TP") (pinfunction "TP_TP") (pintype "input"))
      (node (ref "TP6") (pin "TP") (pinfunction "TP_TP") (pintype "input"))
      (node (ref "U$1") (pin "9") (pinfunction "9_9") (pintype "passive"))
      (node (ref "U$10") (pin "9") (pinfunction "9_9") (pintype "passive"))
      (node (ref "U$11") (pin "9") (pinfunction "9_9") (pintype "passive"))
      (node (ref "U$12") (pin "9") (pinfunction "9_9") (pintype "passive"))
      (node (ref "U$13") (pin "9") (pinfunction "9_9") (pintype "passive"))
      (node (ref "U$14") (pin "9") (pinfunction "9_9") (pintype "passive"))
      (node (ref "U$15") (pin "9") (pinfunction "9_9") (pintype "passive"))
      (node (ref "U$16") (pin "9") (pinfunction "9_9") (pintype "passive"))
      (node (ref "U$2") (pin "9") (pinfunction "9_9") (pintype "passive"))
      (node (ref "U$3") (pin "9") (pinfunction "9_9") (pintype "passive"))
      (node (ref "U$4") (pin "9") (pinfunction "9_9") (pintype "passive"))
      (node (ref "U$5") (pin "9") (pinfunction "9_9") (pintype "passive"))
      (node (ref "U$6") (pin "9") (pinfunction "9_9") (pintype "passive"))
      (node (ref "U$7") (pin "9") (pinfunction "9_9") (pintype "passive"))
      (node (ref "U$8") (pin "9") (pinfunction "9_9") (pintype "passive"))
      (node (ref "U$9") (pin "9") (pinfunction "9_9") (pintype "passive"))
    )
    (net (code "19") (name "HS_GND") (class "Default")
      (node (ref "A-OR-D") (pin "70") (pinfunction "70_70") (pintype "bidirectional"))
      (node (ref "B-OR-C") (pin "70") (pinfunction "70_70") (pintype "bidirectional"))
      (node (ref "GND_IMP") (pin "2") (pinfunction "2_2") (pintype "passive"))
    )
    (net (code "20") (name "ISTIM_A") (class "Default")
      (node (ref "A-OR-D") (pin "69") (pinfunction "69_69") (pintype "bidirectional"))
      (node (ref "CDL_A") (pin "2") (pinfunction "2_2") (pintype "passive"))
      (node (ref "TP14") (pin "TP") (pinfunction "TP_TP") (pintype "input"))
    )
    (net (code "21") (name "ISTIM_B") (class "Default")
      (node (ref "B-OR-C") (pin "69") (pinfunction "69_69") (pintype "bidirectional"))
      (node (ref "CDL_B") (pin "2") (pinfunction "2_2") (pintype "passive"))
      (node (ref "TP15") (pin "TP") (pinfunction "TP_TP") (pintype "input"))
    )
    (net (code "22") (name "Net-(A-OR-D-Pad2)") (class "Default")
      (node (ref "A-OR-D") (pin "2") (pinfunction "2_2") (pintype "bidirectional"))
      (node (ref "R4") (pin "1") (pinfunction "1_1") (pintype "passive"))
      (node (ref "S4") (pin "16") (pinfunction "16_16") (pintype "passive"))
      (node (ref "U$4") (pin "1") (pinfunction "1_1") (pintype "passive"))
    )
    (net (code "23") (name "Net-(A-OR-D-Pad3)") (class "Default")
      (node (ref "A-OR-D") (pin "3") (pinfunction "3_3") (pintype "bidirectional"))
      (node (ref "R4") (pin "2") (pinfunction "2_2") (pintype "passive"))
      (node (ref "S4") (pin "15") (pinfunction "15_15") (pintype "passive"))
      (node (ref "U$4") (pin "2") (pinfunction "2_2") (pintype "passive"))
    )
    (net (code "24") (name "Net-(A-OR-D-Pad4)") (class "Default")
      (node (ref "A-OR-D") (pin "4") (pinfunction "4_4") (pintype "bidirectional"))
      (node (ref "R4") (pin "3") (pinfunction "3_3") (pintype "passive"))
      (node (ref "S4") (pin "14") (pinfunction "14_14") (pintype "passive"))
      (node (ref "U$4") (pin "3") (pinfunction "3_3") (pintype "passive"))
    )
    (net (code "25") (name "Net-(A-OR-D-Pad5)") (class "Default")
      (node (ref "A-OR-D") (pin "5") (pinfunction "5_5") (pintype "bidirectional"))
      (node (ref "R4") (pin "4") (pinfunction "4_4") (pintype "passive"))
      (node (ref "S4") (pin "13") (pinfunction "13_13") (pintype "passive"))
      (node (ref "U$4") (pin "4") (pinfunction "4_4") (pintype "passive"))
    )
    (net (code "26") (name "Net-(A-OR-D-Pad6)") (class "Default")
      (node (ref "A-OR-D") (pin "6") (pinfunction "6_6") (pintype "bidirectional"))
      (node (ref "R4") (pin "5") (pinfunction "5_5") (pintype "passive"))
      (node (ref "S4") (pin "12") (pinfunction "12_12") (pintype "passive"))
      (node (ref "U$4") (pin "5") (pinfunction "5_5") (pintype "passive"))
    )
    (net (code "27") (name "Net-(A-OR-D-Pad7)") (class "Default")
      (node (ref "A-OR-D") (pin "7") (pinfunction "7_7") (pintype "bidirectional"))
      (node (ref "R4") (pin "6") (pinfunction "6_6") (pintype "passive"))
      (node (ref "S4") (pin "11") (pinfunction "11_11") (pintype "passive"))
      (node (ref "U$4") (pin "6") (pinfunction "6_6") (pintype "passive"))
    )
    (net (code "28") (name "Net-(A-OR-D-Pad8)") (class "Default")
      (node (ref "A-OR-D") (pin "8") (pinfunction "8_8") (pintype "bidirectional"))
      (node (ref "R4") (pin "7") (pinfunction "7_7") (pintype "passive"))
      (node (ref "S4") (pin "10") (pinfunction "10_10") (pintype "passive"))
      (node (ref "U$4") (pin "7") (pinfunction "7_7") (pintype "passive"))
    )
    (net (code "29") (name "Net-(A-OR-D-Pad9)") (class "Default")
      (node (ref "A-OR-D") (pin "9") (pinfunction "9_9") (pintype "bidirectional"))
      (node (ref "R4") (pin "8") (pinfunction "8_8") (pintype "passive"))
      (node (ref "S4") (pin "9") (pinfunction "9_9") (pintype "passive"))
      (node (ref "U$4") (pin "8") (pinfunction "8_8") (pintype "passive"))
    )
    (net (code "30") (name "Net-(A-OR-D-Pad10)") (class "Default")
      (node (ref "A-OR-D") (pin "10") (pinfunction "10_10") (pintype "bidirectional"))
      (node (ref "R3") (pin "1") (pinfunction "1_1") (pintype "passive"))
      (node (ref "S3") (pin "16") (pinfunction "16_16") (pintype "passive"))
      (node (ref "U$3") (pin "1") (pinfunction "1_1") (pintype "passive"))
    )
    (net (code "31") (name "Net-(A-OR-D-Pad11)") (class "Default")
      (node (ref "A-OR-D") (pin "11") (pinfunction "11_11") (pintype "bidirectional"))
      (node (ref "R3") (pin "2") (pinfunction "2_2") (pintype "passive"))
      (node (ref "S3") (pin "15") (pinfunction "15_15") (pintype "passive"))
      (node (ref "U$3") (pin "2") (pinfunction "2_2") (pintype "passive"))
    )
    (net (code "32") (name "Net-(A-OR-D-Pad12)") (class "Default")
      (node (ref "A-OR-D") (pin "12") (pinfunction "12_12") (pintype "bidirectional"))
      (node (ref "R3") (pin "3") (pinfunction "3_3") (pintype "passive"))
      (node (ref "S3") (pin "14") (pinfunction "14_14") (pintype "passive"))
      (node (ref "U$3") (pin "3") (pinfunction "3_3") (pintype "passive"))
    )
    (net (code "33") (name "Net-(A-OR-D-Pad13)") (class "Default")
      (node (ref "A-OR-D") (pin "13") (pinfunction "13_13") (pintype "bidirectional"))
      (node (ref "R3") (pin "4") (pinfunction "4_4") (pintype "passive"))
      (node (ref "S3") (pin "13") (pinfunction "13_13") (pintype "passive"))
      (node (ref "U$3") (pin "4") (pinfunction "4_4") (pintype "passive"))
    )
    (net (code "34") (name "Net-(A-OR-D-Pad14)") (class "Default")
      (node (ref "A-OR-D") (pin "14") (pinfunction "14_14") (pintype "bidirectional"))
      (node (ref "R3") (pin "5") (pinfunction "5_5") (pintype "passive"))
      (node (ref "S3") (pin "12") (pinfunction "12_12") (pintype "passive"))
      (node (ref "U$3") (pin "5") (pinfunction "5_5") (pintype "passive"))
    )
    (net (code "35") (name "Net-(A-OR-D-Pad15)") (class "Default")
      (node (ref "A-OR-D") (pin "15") (pinfunction "15_15") (pintype "bidirectional"))
      (node (ref "R3") (pin "6") (pinfunction "6_6") (pintype "passive"))
      (node (ref "S3") (pin "11") (pinfunction "11_11") (pintype "passive"))
      (node (ref "U$3") (pin "6") (pinfunction "6_6") (pintype "passive"))
    )
    (net (code "36") (name "Net-(A-OR-D-Pad16)") (class "Default")
      (node (ref "A-OR-D") (pin "16") (pinfunction "16_16") (pintype "bidirectional"))
      (node (ref "R3") (pin "7") (pinfunction "7_7") (pintype "passive"))
      (node (ref "S3") (pin "10") (pinfunction "10_10") (pintype "passive"))
      (node (ref "U$3") (pin "7") (pinfunction "7_7") (pintype "passive"))
    )
    (net (code "37") (name "Net-(A-OR-D-Pad17)") (class "Default")
      (node (ref "A-OR-D") (pin "17") (pinfunction "17_17") (pintype "bidirectional"))
      (node (ref "R3") (pin "8") (pinfunction "8_8") (pintype "passive"))
      (node (ref "S3") (pin "9") (pinfunction "9_9") (pintype "passive"))
      (node (ref "U$3") (pin "8") (pinfunction "8_8") (pintype "passive"))
    )
    (net (code "38") (name "Net-(A-OR-D-Pad18)") (class "Default")
      (node (ref "A-OR-D") (pin "18") (pinfunction "18_18") (pintype "bidirectional"))
      (node (ref "R2") (pin "1") (pinfunction "1_1") (pintype "passive"))
      (node (ref "S2") (pin "16") (pinfunction "16_16") (pintype "passive"))
      (node (ref "U$2") (pin "1") (pinfunction "1_1") (pintype "passive"))
    )
    (net (code "39") (name "Net-(A-OR-D-Pad19)") (class "Default")
      (node (ref "A-OR-D") (pin "19") (pinfunction "19_19") (pintype "bidirectional"))
      (node (ref "R2") (pin "2") (pinfunction "2_2") (pintype "passive"))
      (node (ref "S2") (pin "15") (pinfunction "15_15") (pintype "passive"))
      (node (ref "U$2") (pin "2") (pinfunction "2_2") (pintype "passive"))
    )
    (net (code "40") (name "Net-(A-OR-D-Pad20)") (class "Default")
      (node (ref "A-OR-D") (pin "20") (pinfunction "20_20") (pintype "bidirectional"))
      (node (ref "R2") (pin "3") (pinfunction "3_3") (pintype "passive"))
      (node (ref "S2") (pin "14") (pinfunction "14_14") (pintype "passive"))
      (node (ref "U$2") (pin "3") (pinfunction "3_3") (pintype "passive"))
    )
    (net (code "41") (name "Net-(A-OR-D-Pad21)") (class "Default")
      (node (ref "A-OR-D") (pin "21") (pinfunction "21_21") (pintype "bidirectional"))
      (node (ref "R2") (pin "4") (pinfunction "4_4") (pintype "passive"))
      (node (ref "S2") (pin "13") (pinfunction "13_13") (pintype "passive"))
      (node (ref "U$2") (pin "4") (pinfunction "4_4") (pintype "passive"))
    )
    (net (code "42") (name "Net-(A-OR-D-Pad22)") (class "Default")
      (node (ref "A-OR-D") (pin "22") (pinfunction "22_22") (pintype "bidirectional"))
      (node (ref "R2") (pin "5") (pinfunction "5_5") (pintype "passive"))
      (node (ref "S2") (pin "12") (pinfunction "12_12") (pintype "passive"))
      (node (ref "U$2") (pin "5") (pinfunction "5_5") (pintype "passive"))
    )
    (net (code "43") (name "Net-(A-OR-D-Pad23)") (class "Default")
      (node (ref "A-OR-D") (pin "23") (pinfunction "23_23") (pintype "bidirectional"))
      (node (ref "R2") (pin "6") (pinfunction "6_6") (pintype "passive"))
      (node (ref "S2") (pin "11") (pinfunction "11_11") (pintype "passive"))
      (node (ref "U$2") (pin "6") (pinfunction "6_6") (pintype "passive"))
    )
    (net (code "44") (name "Net-(A-OR-D-Pad24)") (class "Default")
      (node (ref "A-OR-D") (pin "24") (pinfunction "24_24") (pintype "bidirectional"))
      (node (ref "R2") (pin "7") (pinfunction "7_7") (pintype "passive"))
      (node (ref "S2") (pin "10") (pinfunction "10_10") (pintype "passive"))
      (node (ref "U$2") (pin "7") (pinfunction "7_7") (pintype "passive"))
    )
    (net (code "45") (name "Net-(A-OR-D-Pad25)") (class "Default")
      (node (ref "A-OR-D") (pin "25") (pinfunction "25_25") (pintype "bidirectional"))
      (node (ref "R2") (pin "8") (pinfunction "8_8") (pintype "passive"))
      (node (ref "S2") (pin "9") (pinfunction "9_9") (pintype "passive"))
      (node (ref "U$2") (pin "8") (pinfunction "8_8") (pintype "passive"))
    )
    (net (code "46") (name "Net-(A-OR-D-Pad26)") (class "Default")
      (node (ref "A-OR-D") (pin "26") (pinfunction "26_26") (pintype "bidirectional"))
      (node (ref "R1") (pin "1") (pinfunction "1_1") (pintype "passive"))
      (node (ref "S1") (pin "16") (pinfunction "16_16") (pintype "passive"))
      (node (ref "U$1") (pin "1") (pinfunction "1_1") (pintype "passive"))
    )
    (net (code "47") (name "Net-(A-OR-D-Pad27)") (class "Default")
      (node (ref "A-OR-D") (pin "27") (pinfunction "27_27") (pintype "bidirectional"))
      (node (ref "R1") (pin "2") (pinfunction "2_2") (pintype "passive"))
      (node (ref "S1") (pin "15") (pinfunction "15_15") (pintype "passive"))
      (node (ref "U$1") (pin "2") (pinfunction "2_2") (pintype "passive"))
    )
    (net (code "48") (name "Net-(A-OR-D-Pad28)") (class "Default")
      (node (ref "A-OR-D") (pin "28") (pinfunction "28_28") (pintype "bidirectional"))
      (node (ref "R1") (pin "3") (pinfunction "3_3") (pintype "passive"))
      (node (ref "S1") (pin "14") (pinfunction "14_14") (pintype "passive"))
      (node (ref "U$1") (pin "3") (pinfunction "3_3") (pintype "passive"))
    )
    (net (code "49") (name "Net-(A-OR-D-Pad29)") (class "Default")
      (node (ref "A-OR-D") (pin "29") (pinfunction "29_29") (pintype "bidirectional"))
      (node (ref "R1") (pin "4") (pinfunction "4_4") (pintype "passive"))
      (node (ref "S1") (pin "13") (pinfunction "13_13") (pintype "passive"))
      (node (ref "U$1") (pin "4") (pinfunction "4_4") (pintype "passive"))
    )
    (net (code "50") (name "Net-(A-OR-D-Pad30)") (class "Default")
      (node (ref "A-OR-D") (pin "30") (pinfunction "30_30") (pintype "bidirectional"))
      (node (ref "R1") (pin "5") (pinfunction "5_5") (pintype "passive"))
      (node (ref "S1") (pin "12") (pinfunction "12_12") (pintype "passive"))
      (node (ref "U$1") (pin "5") (pinfunction "5_5") (pintype "passive"))
    )
    (net (code "51") (name "Net-(A-OR-D-Pad31)") (class "Default")
      (node (ref "A-OR-D") (pin "31") (pinfunction "31_31") (pintype "bidirectional"))
      (node (ref "R1") (pin "6") (pinfunction "6_6") (pintype "passive"))
      (node (ref "S1") (pin "11") (pinfunction "11_11") (pintype "passive"))
      (node (ref "U$1") (pin "6") (pinfunction "6_6") (pintype "passive"))
    )
    (net (code "52") (name "Net-(A-OR-D-Pad32)") (class "Default")
      (node (ref "A-OR-D") (pin "32") (pinfunction "32_32") (pintype "bidirectional"))
      (node (ref "R1") (pin "7") (pinfunction "7_7") (pintype "passive"))
      (node (ref "S1") (pin "10") (pinfunction "10_10") (pintype "passive"))
      (node (ref "U$1") (pin "7") (pinfunction "7_7") (pintype "passive"))
    )
    (net (code "53") (name "Net-(A-OR-D-Pad33)") (class "Default")
      (node (ref "A-OR-D") (pin "33") (pinfunction "33_33") (pintype "bidirectional"))
      (node (ref "R1") (pin "8") (pinfunction "8_8") (pintype "passive"))
      (node (ref "S1") (pin "9") (pinfunction "9_9") (pintype "passive"))
      (node (ref "U$1") (pin "8") (pinfunction "8_8") (pintype "passive"))
    )
    (net (code "54") (name "Net-(A-OR-D-Pad37)") (class "Default")
      (node (ref "A-OR-D") (pin "37") (pinfunction "37_37") (pintype "bidirectional"))
      (node (ref "R5") (pin "1") (pinfunction "1_1") (pintype "passive"))
      (node (ref "S5") (pin "16") (pinfunction "16_16") (pintype "passive"))
      (node (ref "U$5") (pin "1") (pinfunction "1_1") (pintype "passive"))
    )
    (net (code "55") (name "Net-(A-OR-D-Pad38)") (class "Default")
      (node (ref "A-OR-D") (pin "38") (pinfunction "38_38") (pintype "bidirectional"))
      (node (ref "R5") (pin "2") (pinfunction "2_2") (pintype "passive"))
      (node (ref "S5") (pin "15") (pinfunction "15_15") (pintype "passive"))
      (node (ref "U$5") (pin "2") (pinfunction "2_2") (pintype "passive"))
    )
    (net (code "56") (name "Net-(A-OR-D-Pad39)") (class "Default")
      (node (ref "A-OR-D") (pin "39") (pinfunction "39_39") (pintype "bidirectional"))
      (node (ref "R5") (pin "3") (pinfunction "3_3") (pintype "passive"))
      (node (ref "S5") (pin "14") (pinfunction "14_14") (pintype "passive"))
      (node (ref "U$5") (pin "3") (pinfunction "3_3") (pintype "passive"))
    )
    (net (code "57") (name "Net-(A-OR-D-Pad40)") (class "Default")
      (node (ref "A-OR-D") (pin "40") (pinfunction "40_40") (pintype "bidirectional"))
      (node (ref "R5") (pin "4") (pinfunction "4_4") (pintype "passive"))
      (node (ref "S5") (pin "13") (pinfunction "13_13") (pintype "passive"))
      (node (ref "U$5") (pin "4") (pinfunction "4_4") (pintype "passive"))
    )
    (net (code "58") (name "Net-(A-OR-D-Pad41)") (class "Default")
      (node (ref "A-OR-D") (pin "41") (pinfunction "41_41") (pintype "bidirectional"))
      (node (ref "R5") (pin "5") (pinfunction "5_5") (pintype "passive"))
      (node (ref "S5") (pin "12") (pinfunction "12_12") (pintype "passive"))
      (node (ref "U$5") (pin "5") (pinfunction "5_5") (pintype "passive"))
    )
    (net (code "59") (name "Net-(A-OR-D-Pad42)") (class "Default")
      (node (ref "A-OR-D") (pin "42") (pinfunction "42_42") (pintype "bidirectional"))
      (node (ref "R5") (pin "6") (pinfunction "6_6") (pintype "passive"))
      (node (ref "S5") (pin "11") (pinfunction "11_11") (pintype "passive"))
      (node (ref "U$5") (pin "6") (pinfunction "6_6") (pintype "passive"))
    )
    (net (code "60") (name "Net-(A-OR-D-Pad43)") (class "Default")
      (node (ref "A-OR-D") (pin "43") (pinfunction "43_43") (pintype "bidirectional"))
      (node (ref "R5") (pin "7") (pinfunction "7_7") (pintype "passive"))
      (node (ref "S5") (pin "10") (pinfunction "10_10") (pintype "passive"))
      (node (ref "U$5") (pin "7") (pinfunction "7_7") (pintype "passive"))
    )
    (net (code "61") (name "Net-(A-OR-D-Pad44)") (class "Default")
      (node (ref "A-OR-D") (pin "44") (pinfunction "44_44") (pintype "bidirectional"))
      (node (ref "R5") (pin "8") (pinfunction "8_8") (pintype "passive"))
      (node (ref "S5") (pin "9") (pinfunction "9_9") (pintype "passive"))
      (node (ref "U$5") (pin "8") (pinfunction "8_8") (pintype "passive"))
    )
    (net (code "62") (name "Net-(A-OR-D-Pad45)") (class "Default")
      (node (ref "A-OR-D") (pin "45") (pinfunction "45_45") (pintype "bidirectional"))
      (node (ref "R6") (pin "1") (pinfunction "1_1") (pintype "passive"))
      (node (ref "S6") (pin "16") (pinfunction "16_16") (pintype "passive"))
      (node (ref "U$6") (pin "1") (pinfunction "1_1") (pintype "passive"))
    )
    (net (code "63") (name "Net-(A-OR-D-Pad46)") (class "Default")
      (node (ref "A-OR-D") (pin "46") (pinfunction "46_46") (pintype "bidirectional"))
      (node (ref "R6") (pin "2") (pinfunction "2_2") (pintype "passive"))
      (node (ref "S6") (pin "15") (pinfunction "15_15") (pintype "passive"))
      (node (ref "U$6") (pin "2") (pinfunction "2_2") (pintype "passive"))
    )
    (net (code "64") (name "Net-(A-OR-D-Pad47)") (class "Default")
      (node (ref "A-OR-D") (pin "47") (pinfunction "47_47") (pintype "bidirectional"))
      (node (ref "R6") (pin "3") (pinfunction "3_3") (pintype "passive"))
      (node (ref "S6") (pin "14") (pinfunction "14_14") (pintype "passive"))
      (node (ref "U$6") (pin "3") (pinfunction "3_3") (pintype "passive"))
    )
    (net (code "65") (name "Net-(A-OR-D-Pad48)") (class "Default")
      (node (ref "A-OR-D") (pin "48") (pinfunction "48_48") (pintype "bidirectional"))
      (node (ref "R6") (pin "4") (pinfunction "4_4") (pintype "passive"))
      (node (ref "S6") (pin "13") (pinfunction "13_13") (pintype "passive"))
      (node (ref "U$6") (pin "4") (pinfunction "4_4") (pintype "passive"))
    )
    (net (code "66") (name "Net-(A-OR-D-Pad49)") (class "Default")
      (node (ref "A-OR-D") (pin "49") (pinfunction "49_49") (pintype "bidirectional"))
      (node (ref "R6") (pin "5") (pinfunction "5_5") (pintype "passive"))
      (node (ref "S6") (pin "12") (pinfunction "12_12") (pintype "passive"))
      (node (ref "U$6") (pin "5") (pinfunction "5_5") (pintype "passive"))
    )
    (net (code "67") (name "Net-(A-OR-D-Pad50)") (class "Default")
      (node (ref "A-OR-D") (pin "50") (pinfunction "50_50") (pintype "bidirectional"))
      (node (ref "R6") (pin "6") (pinfunction "6_6") (pintype "passive"))
      (node (ref "S6") (pin "11") (pinfunction "11_11") (pintype "passive"))
      (node (ref "U$6") (pin "6") (pinfunction "6_6") (pintype "passive"))
    )
    (net (code "68") (name "Net-(A-OR-D-Pad51)") (class "Default")
      (node (ref "A-OR-D") (pin "51") (pinfunction "51_51") (pintype "bidirectional"))
      (node (ref "R6") (pin "7") (pinfunction "7_7") (pintype "passive"))
      (node (ref "S6") (pin "10") (pinfunction "10_10") (pintype "passive"))
      (node (ref "U$6") (pin "7") (pinfunction "7_7") (pintype "passive"))
    )
    (net (code "69") (name "Net-(A-OR-D-Pad52)") (class "Default")
      (node (ref "A-OR-D") (pin "52") (pinfunction "52_52") (pintype "bidirectional"))
      (node (ref "R6") (pin "8") (pinfunction "8_8") (pintype "passive"))
      (node (ref "S6") (pin "9") (pinfunction "9_9") (pintype "passive"))
      (node (ref "U$6") (pin "8") (pinfunction "8_8") (pintype "passive"))
    )
    (net (code "70") (name "Net-(A-OR-D-Pad53)") (class "Default")
      (node (ref "A-OR-D") (pin "53") (pinfunction "53_53") (pintype "bidirectional"))
      (node (ref "R7") (pin "1") (pinfunction "1_1") (pintype "passive"))
      (node (ref "S7") (pin "16") (pinfunction "16_16") (pintype "passive"))
      (node (ref "U$7") (pin "1") (pinfunction "1_1") (pintype "passive"))
    )
    (net (code "71") (name "Net-(A-OR-D-Pad54)") (class "Default")
      (node (ref "A-OR-D") (pin "54") (pinfunction "54_54") (pintype "bidirectional"))
      (node (ref "R7") (pin "2") (pinfunction "2_2") (pintype "passive"))
      (node (ref "S7") (pin "15") (pinfunction "15_15") (pintype "passive"))
      (node (ref "U$7") (pin "2") (pinfunction "2_2") (pintype "passive"))
    )
    (net (code "72") (name "Net-(A-OR-D-Pad55)") (class "Default")
      (node (ref "A-OR-D") (pin "55") (pinfunction "55_55") (pintype "bidirectional"))
      (node (ref "R7") (pin "3") (pinfunction "3_3") (pintype "passive"))
      (node (ref "S7") (pin "14") (pinfunction "14_14") (pintype "passive"))
      (node (ref "U$7") (pin "3") (pinfunction "3_3") (pintype "passive"))
    )
    (net (code "73") (name "Net-(A-OR-D-Pad56)") (class "Default")
      (node (ref "A-OR-D") (pin "56") (pinfunction "56_56") (pintype "bidirectional"))
      (node (ref "R7") (pin "4") (pinfunction "4_4") (pintype "passive"))
      (node (ref "S7") (pin "13") (pinfunction "13_13") (pintype "passive"))
      (node (ref "U$7") (pin "4") (pinfunction "4_4") (pintype "passive"))
    )
    (net (code "74") (name "Net-(A-OR-D-Pad57)") (class "Default")
      (node (ref "A-OR-D") (pin "57") (pinfunction "57_57") (pintype "bidirectional"))
      (node (ref "R7") (pin "5") (pinfunction "5_5") (pintype "passive"))
      (node (ref "S7") (pin "12") (pinfunction "12_12") (pintype "passive"))
      (node (ref "U$7") (pin "5") (pinfunction "5_5") (pintype "passive"))
    )
    (net (code "75") (name "Net-(A-OR-D-Pad58)") (class "Default")
      (node (ref "A-OR-D") (pin "58") (pinfunction "58_58") (pintype "bidirectional"))
      (node (ref "R7") (pin "6") (pinfunction "6_6") (pintype "passive"))
      (node (ref "S7") (pin "11") (pinfunction "11_11") (pintype "passive"))
      (node (ref "U$7") (pin "6") (pinfunction "6_6") (pintype "passive"))
    )
    (net (code "76") (name "Net-(A-OR-D-Pad59)") (class "Default")
      (node (ref "A-OR-D") (pin "59") (pinfunction "59_59") (pintype "bidirectional"))
      (node (ref "R7") (pin "7") (pinfunction "7_7") (pintype "passive"))
      (node (ref "S7") (pin "10") (pinfunction "10_10") (pintype "passive"))
      (node (ref "U$7") (pin "7") (pinfunction "7_7") (pintype "passive"))
    )
    (net (code "77") (name "Net-(A-OR-D-Pad60)") (class "Default")
      (node (ref "A-OR-D") (pin "60") (pinfunction "60_60") (pintype "bidirectional"))
      (node (ref "R7") (pin "8") (pinfunction "8_8") (pintype "passive"))
      (node (ref "S7") (pin "9") (pinfunction "9_9") (pintype "passive"))
      (node (ref "U$7") (pin "8") (pinfunction "8_8") (pintype "passive"))
    )
    (net (code "78") (name "Net-(A-OR-D-Pad61)") (class "Default")
      (node (ref "A-OR-D") (pin "61") (pinfunction "61_61") (pintype "bidirectional"))
      (node (ref "R8") (pin "1") (pinfunction "1_1") (pintype "passive"))
      (node (ref "S8") (pin "16") (pinfunction "16_16") (pintype "passive"))
      (node (ref "U$8") (pin "1") (pinfunction "1_1") (pintype "passive"))
    )
    (net (code "79") (name "Net-(A-OR-D-Pad62)") (class "Default")
      (node (ref "A-OR-D") (pin "62") (pinfunction "62_62") (pintype "bidirectional"))
      (node (ref "R8") (pin "2") (pinfunction "2_2") (pintype "passive"))
      (node (ref "S8") (pin "15") (pinfunction "15_15") (pintype "passive"))
      (node (ref "U$8") (pin "2") (pinfunction "2_2") (pintype "passive"))
    )
    (net (code "80") (name "Net-(A-OR-D-Pad63)") (class "Default")
      (node (ref "A-OR-D") (pin "63") (pinfunction "63_63") (pintype "bidirectional"))
      (node (ref "R8") (pin "3") (pinfunction "3_3") (pintype "passive"))
      (node (ref "S8") (pin "14") (pinfunction "14_14") (pintype "passive"))
      (node (ref "U$8") (pin "3") (pinfunction "3_3") (pintype "passive"))
    )
    (net (code "81") (name "Net-(A-OR-D-Pad64)") (class "Default")
      (node (ref "A-OR-D") (pin "64") (pinfunction "64_64") (pintype "bidirectional"))
      (node (ref "R8") (pin "4") (pinfunction "4_4") (pintype "passive"))
      (node (ref "S8") (pin "13") (pinfunction "13_13") (pintype "passive"))
      (node (ref "U$8") (pin "4") (pinfunction "4_4") (pintype "passive"))
    )
    (net (code "82") (name "Net-(A-OR-D-Pad65)") (class "Default")
      (node (ref "A-OR-D") (pin "65") (pinfunction "65_65") (pintype "bidirectional"))
      (node (ref "R8") (pin "5") (pinfunction "5_5") (pintype "passive"))
      (node (ref "S8") (pin "12") (pinfunction "12_12") (pintype "passive"))
      (node (ref "U$8") (pin "5") (pinfunction "5_5") (pintype "passive"))
    )
    (net (code "83") (name "Net-(A-OR-D-Pad66)") (class "Default")
      (node (ref "A-OR-D") (pin "66") (pinfunction "66_66") (pintype "bidirectional"))
      (node (ref "R8") (pin "6") (pinfunction "6_6") (pintype "passive"))
      (node (ref "S8") (pin "11") (pinfunction "11_11") (pintype "passive"))
      (node (ref "U$8") (pin "6") (pinfunction "6_6") (pintype "passive"))
    )
    (net (code "84") (name "Net-(A-OR-D-Pad67)") (class "Default")
      (node (ref "A-OR-D") (pin "67") (pinfunction "67_67") (pintype "bidirectional"))
      (node (ref "R8") (pin "7") (pinfunction "7_7") (pintype "passive"))
      (node (ref "S8") (pin "10") (pinfunction "10_10") (pintype "passive"))
      (node (ref "U$8") (pin "7") (pinfunction "7_7") (pintype "passive"))
    )
    (net (code "85") (name "Net-(A-OR-D-Pad68)") (class "Default")
      (node (ref "A-OR-D") (pin "68") (pinfunction "68_68") (pintype "bidirectional"))
      (node (ref "R8") (pin "8") (pinfunction "8_8") (pintype "passive"))
      (node (ref "S8") (pin "9") (pinfunction "9_9") (pintype "passive"))
      (node (ref "U$8") (pin "8") (pinfunction "8_8") (pintype "passive"))
    )
    (net (code "86") (name "Net-(B-OR-C-Pad2)") (class "Default")
      (node (ref "B-OR-C") (pin "2") (pinfunction "2_2") (pintype "bidirectional"))
      (node (ref "R13") (pin "1") (pinfunction "1_1") (pintype "passive"))
      (node (ref "S13") (pin "16") (pinfunction "16_16") (pintype "passive"))
      (node (ref "U$13") (pin "1") (pinfunction "1_1") (pintype "passive"))
    )
    (net (code "87") (name "Net-(B-OR-C-Pad3)") (class "Default")
      (node (ref "B-OR-C") (pin "3") (pinfunction "3_3") (pintype "bidirectional"))
      (node (ref "R13") (pin "2") (pinfunction "2_2") (pintype "passive"))
      (node (ref "S13") (pin "15") (pinfunction "15_15") (pintype "passive"))
      (node (ref "U$13") (pin "2") (pinfunction "2_2") (pintype "passive"))
    )
    (net (code "88") (name "Net-(B-OR-C-Pad4)") (class "Default")
      (node (ref "B-OR-C") (pin "4") (pinfunction "4_4") (pintype "bidirectional"))
      (node (ref "R13") (pin "3") (pinfunction "3_3") (pintype "passive"))
      (node (ref "S13") (pin "14") (pinfunction "14_14") (pintype "passive"))
      (node (ref "U$13") (pin "3") (pinfunction "3_3") (pintype "passive"))
    )
    (net (code "89") (name "Net-(B-OR-C-Pad5)") (class "Default")
      (node (ref "B-OR-C") (pin "5") (pinfunction "5_5") (pintype "bidirectional"))
      (node (ref "R13") (pin "4") (pinfunction "4_4") (pintype "passive"))
      (node (ref "S13") (pin "13") (pinfunction "13_13") (pintype "passive"))
      (node (ref "U$13") (pin "4") (pinfunction "4_4") (pintype "passive"))
    )
    (net (code "90") (name "Net-(B-OR-C-Pad6)") (class "Default")
      (node (ref "B-OR-C") (pin "6") (pinfunction "6_6") (pintype "bidirectional"))
      (node (ref "R13") (pin "5") (pinfunction "5_5") (pintype "passive"))
      (node (ref "S13") (pin "12") (pinfunction "12_12") (pintype "passive"))
      (node (ref "U$13") (pin "5") (pinfunction "5_5") (pintype "passive"))
    )
    (net (code "91") (name "Net-(B-OR-C-Pad7)") (class "Default")
      (node (ref "B-OR-C") (pin "7") (pinfunction "7_7") (pintype "bidirectional"))
      (node (ref "R13") (pin "6") (pinfunction "6_6") (pintype "passive"))
      (node (ref "S13") (pin "11") (pinfunction "11_11") (pintype "passive"))
      (node (ref "U$13") (pin "6") (pinfunction "6_6") (pintype "passive"))
    )
    (net (code "92") (name "Net-(B-OR-C-Pad8)") (class "Default")
      (node (ref "B-OR-C") (pin "8") (pinfunction "8_8") (pintype "bidirectional"))
      (node (ref "R13") (pin "7") (pinfunction "7_7") (pintype "passive"))
      (node (ref "S13") (pin "10") (pinfunction "10_10") (pintype "passive"))
      (node (ref "U$13") (pin "7") (pinfunction "7_7") (pintype "passive"))
    )
    (net (code "93") (name "Net-(B-OR-C-Pad9)") (class "Default")
      (node (ref "B-OR-C") (pin "9") (pinfunction "9_9") (pintype "bidirectional"))
      (node (ref "R13") (pin "8") (pinfunction "8_8") (pintype "passive"))
      (node (ref "S13") (pin "9") (pinfunction "9_9") (pintype "passive"))
      (node (ref "U$13") (pin "8") (pinfunction "8_8") (pintype "passive"))
    )
    (net (code "94") (name "Net-(B-OR-C-Pad10)") (class "Default")
      (node (ref "B-OR-C") (pin "10") (pinfunction "10_10") (pintype "bidirectional"))
      (node (ref "R14") (pin "1") (pinfunction "1_1") (pintype "passive"))
      (node (ref "S14") (pin "16") (pinfunction "16_16") (pintype "passive"))
      (node (ref "U$14") (pin "1") (pinfunction "1_1") (pintype "passive"))
    )
    (net (code "95") (name "Net-(B-OR-C-Pad11)") (class "Default")
      (node (ref "B-OR-C") (pin "11") (pinfunction "11_11") (pintype "bidirectional"))
      (node (ref "R14") (pin "2") (pinfunction "2_2") (pintype "passive"))
      (node (ref "S14") (pin "15") (pinfunction "15_15") (pintype "passive"))
      (node (ref "U$14") (pin "2") (pinfunction "2_2") (pintype "passive"))
    )
    (net (code "96") (name "Net-(B-OR-C-Pad12)") (class "Default")
      (node (ref "B-OR-C") (pin "12") (pinfunction "12_12") (pintype "bidirectional"))
      (node (ref "R14") (pin "3") (pinfunction "3_3") (pintype "passive"))
      (node (ref "S14") (pin "14") (pinfunction "14_14") (pintype "passive"))
      (node (ref "U$14") (pin "3") (pinfunction "3_3") (pintype "passive"))
    )
    (net (code "97") (name "Net-(B-OR-C-Pad13)") (class "Default")
      (node (ref "B-OR-C") (pin "13") (pinfunction "13_13") (pintype "bidirectional"))
      (node (ref "R14") (pin "4") (pinfunction "4_4") (pintype "passive"))
      (node (ref "S14") (pin "13") (pinfunction "13_13") (pintype "passive"))
      (node (ref "U$14") (pin "4") (pinfunction "4_4") (pintype "passive"))
    )
    (net (code "98") (name "Net-(B-OR-C-Pad14)") (class "Default")
      (node (ref "B-OR-C") (pin "14") (pinfunction "14_14") (pintype "bidirectional"))
      (node (ref "R14") (pin "5") (pinfunction "5_5") (pintype "passive"))
      (node (ref "S14") (pin "12") (pinfunction "12_12") (pintype "passive"))
      (node (ref "U$14") (pin "5") (pinfunction "5_5") (pintype "passive"))
    )
    (net (code "99") (name "Net-(B-OR-C-Pad15)") (class "Default")
      (node (ref "B-OR-C") (pin "15") (pinfunction "15_15") (pintype "bidirectional"))
      (node (ref "R14") (pin "6") (pinfunction "6_6") (pintype "passive"))
      (node (ref "S14") (pin "11") (pinfunction "11_11") (pintype "passive"))
      (node (ref "U$14") (pin "6") (pinfunction "6_6") (pintype "passive"))
    )
    (net (code "100") (name "Net-(B-OR-C-Pad16)") (class "Default")
      (node (ref "B-OR-C") (pin "16") (pinfunction "16_16") (pintype "bidirectional"))
      (node (ref "R14") (pin "7") (pinfunction "7_7") (pintype "passive"))
      (node (ref "S14") (pin "10") (pinfunction "10_10") (pintype "passive"))
      (node (ref "U$14") (pin "7") (pinfunction "7_7") (pintype "passive"))
    )
    (net (code "101") (name "Net-(B-OR-C-Pad17)") (class "Default")
      (node (ref "B-OR-C") (pin "17") (pinfunction "17_17") (pintype "bidirectional"))
      (node (ref "R14") (pin "8") (pinfunction "8_8") (pintype "passive"))
      (node (ref "S14") (pin "9") (pinfunction "9_9") (pintype "passive"))
      (node (ref "U$14") (pin "8") (pinfunction "8_8") (pintype "passive"))
    )
    (net (code "102") (name "Net-(B-OR-C-Pad18)") (class "Default")
      (node (ref "B-OR-C") (pin "18") (pinfunction "18_18") (pintype "bidirectional"))
      (node (ref "R15") (pin "1") (pinfunction "1_1") (pintype "passive"))
      (node (ref "S15") (pin "16") (pinfunction "16_16") (pintype "passive"))
      (node (ref "U$15") (pin "1") (pinfunction "1_1") (pintype "passive"))
    )
    (net (code "103") (name "Net-(B-OR-C-Pad19)") (class "Default")
      (node (ref "B-OR-C") (pin "19") (pinfunction "19_19") (pintype "bidirectional"))
      (node (ref "R15") (pin "2") (pinfunction "2_2") (pintype "passive"))
      (node (ref "S15") (pin "15") (pinfunction "15_15") (pintype "passive"))
      (node (ref "U$15") (pin "2") (pinfunction "2_2") (pintype "passive"))
    )
    (net (code "104") (name "Net-(B-OR-C-Pad20)") (class "Default")
      (node (ref "B-OR-C") (pin "20") (pinfunction "20_20") (pintype "bidirectional"))
      (node (ref "R15") (pin "3") (pinfunction "3_3") (pintype "passive"))
      (node (ref "S15") (pin "14") (pinfunction "14_14") (pintype "passive"))
      (node (ref "U$15") (pin "3") (pinfunction "3_3") (pintype "passive"))
    )
    (net (code "105") (name "Net-(B-OR-C-Pad21)") (class "Default")
      (node (ref "B-OR-C") (pin "21") (pinfunction "21_21") (pintype "bidirectional"))
      (node (ref "R15") (pin "4") (pinfunction "4_4") (pintype "passive"))
      (node (ref "S15") (pin "13") (pinfunction "13_13") (pintype "passive"))
      (node (ref "U$15") (pin "4") (pinfunction "4_4") (pintype "passive"))
    )
    (net (code "106") (name "Net-(B-OR-C-Pad22)") (class "Default")
      (node (ref "B-OR-C") (pin "22") (pinfunction "22_22") (pintype "bidirectional"))
      (node (ref "R15") (pin "5") (pinfunction "5_5") (pintype "passive"))
      (node (ref "S15") (pin "12") (pinfunction "12_12") (pintype "passive"))
      (node (ref "U$15") (pin "5") (pinfunction "5_5") (pintype "passive"))
    )
    (net (code "107") (name "Net-(B-OR-C-Pad23)") (class "Default")
      (node (ref "B-OR-C") (pin "23") (pinfunction "23_23") (pintype "bidirectional"))
      (node (ref "R15") (pin "6") (pinfunction "6_6") (pintype "passive"))
      (node (ref "S15") (pin "11") (pinfunction "11_11") (pintype "passive"))
      (node (ref "U$15") (pin "6") (pinfunction "6_6") (pintype "passive"))
    )
    (net (code "108") (name "Net-(B-OR-C-Pad24)") (class "Default")
      (node (ref "B-OR-C") (pin "24") (pinfunction "24_24") (pintype "bidirectional"))
      (node (ref "R15") (pin "7") (pinfunction "7_7") (pintype "passive"))
      (node (ref "S15") (pin "10") (pinfunction "10_10") (pintype "passive"))
      (node (ref "U$15") (pin "7") (pinfunction "7_7") (pintype "passive"))
    )
    (net (code "109") (name "Net-(B-OR-C-Pad25)") (class "Default")
      (node (ref "B-OR-C") (pin "25") (pinfunction "25_25") (pintype "bidirectional"))
      (node (ref "R15") (pin "8") (pinfunction "8_8") (pintype "passive"))
      (node (ref "S15") (pin "9") (pinfunction "9_9") (pintype "passive"))
      (node (ref "U$15") (pin "8") (pinfunction "8_8") (pintype "passive"))
    )
    (net (code "110") (name "Net-(B-OR-C-Pad26)") (class "Default")
      (node (ref "B-OR-C") (pin "26") (pinfunction "26_26") (pintype "bidirectional"))
      (node (ref "R16") (pin "1") (pinfunction "1_1") (pintype "passive"))
      (node (ref "S16") (pin "16") (pinfunction "16_16") (pintype "passive"))
      (node (ref "U$16") (pin "1") (pinfunction "1_1") (pintype "passive"))
    )
    (net (code "111") (name "Net-(B-OR-C-Pad27)") (class "Default")
      (node (ref "B-OR-C") (pin "27") (pinfunction "27_27") (pintype "bidirectional"))
      (node (ref "R16") (pin "2") (pinfunction "2_2") (pintype "passive"))
      (node (ref "S16") (pin "15") (pinfunction "15_15") (pintype "passive"))
      (node (ref "U$16") (pin "2") (pinfunction "2_2") (pintype "passive"))
    )
    (net (code "112") (name "Net-(B-OR-C-Pad28)") (class "Default")
      (node (ref "B-OR-C") (pin "28") (pinfunction "28_28") (pintype "bidirectional"))
      (node (ref "R16") (pin "3") (pinfunction "3_3") (pintype "passive"))
      (node (ref "S16") (pin "14") (pinfunction "14_14") (pintype "passive"))
      (node (ref "U$16") (pin "3") (pinfunction "3_3") (pintype "passive"))
    )
    (net (code "113") (name "Net-(B-OR-C-Pad29)") (class "Default")
      (node (ref "B-OR-C") (pin "29") (pinfunction "29_29") (pintype "bidirectional"))
      (node (ref "R16") (pin "4") (pinfunction "4_4") (pintype "passive"))
      (node (ref "S16") (pin "13") (pinfunction "13_13") (pintype "passive"))
      (node (ref "U$16") (pin "4") (pinfunction "4_4") (pintype "passive"))
    )
    (net (code "114") (name "Net-(B-OR-C-Pad30)") (class "Default")
      (node (ref "B-OR-C") (pin "30") (pinfunction "30_30") (pintype "bidirectional"))
      (node (ref "R16") (pin "5") (pinfunction "5_5") (pintype "passive"))
      (node (ref "S16") (pin "12") (pinfunction "12_12") (pintype "passive"))
      (node (ref "U$16") (pin "5") (pinfunction "5_5") (pintype "passive"))
    )
    (net (code "115") (name "Net-(B-OR-C-Pad31)") (class "Default")
      (node (ref "B-OR-C") (pin "31") (pinfunction "31_31") (pintype "bidirectional"))
      (node (ref "R16") (pin "6") (pinfunction "6_6") (pintype "passive"))
      (node (ref "S16") (pin "11") (pinfunction "11_11") (pintype "passive"))
      (node (ref "U$16") (pin "6") (pinfunction "6_6") (pintype "passive"))
    )
    (net (code "116") (name "Net-(B-OR-C-Pad32)") (class "Default")
      (node (ref "B-OR-C") (pin "32") (pinfunction "32_32") (pintype "bidirectional"))
      (node (ref "R16") (pin "7") (pinfunction "7_7") (pintype "passive"))
      (node (ref "S16") (pin "10") (pinfunction "10_10") (pintype "passive"))
      (node (ref "U$16") (pin "7") (pinfunction "7_7") (pintype "passive"))
    )
    (net (code "117") (name "Net-(B-OR-C-Pad33)") (class "Default")
      (node (ref "B-OR-C") (pin "33") (pinfunction "33_33") (pintype "bidirectional"))
      (node (ref "R16") (pin "8") (pinfunction "8_8") (pintype "passive"))
      (node (ref "S16") (pin "9") (pinfunction "9_9") (pintype "passive"))
      (node (ref "U$16") (pin "8") (pinfunction "8_8") (pintype "passive"))
    )
    (net (code "118") (name "Net-(B-OR-C-Pad37)") (class "Default")
      (node (ref "B-OR-C") (pin "37") (pinfunction "37_37") (pintype "bidirectional"))
      (node (ref "R12") (pin "1") (pinfunction "1_1") (pintype "passive"))
      (node (ref "S12") (pin "16") (pinfunction "16_16") (pintype "passive"))
      (node (ref "U$12") (pin "1") (pinfunction "1_1") (pintype "passive"))
    )
    (net (code "119") (name "Net-(B-OR-C-Pad38)") (class "Default")
      (node (ref "B-OR-C") (pin "38") (pinfunction "38_38") (pintype "bidirectional"))
      (node (ref "R12") (pin "2") (pinfunction "2_2") (pintype "passive"))
      (node (ref "S12") (pin "15") (pinfunction "15_15") (pintype "passive"))
      (node (ref "U$12") (pin "2") (pinfunction "2_2") (pintype "passive"))
    )
    (net (code "120") (name "Net-(B-OR-C-Pad39)") (class "Default")
      (node (ref "B-OR-C") (pin "39") (pinfunction "39_39") (pintype "bidirectional"))
      (node (ref "R12") (pin "3") (pinfunction "3_3") (pintype "passive"))
      (node (ref "S12") (pin "14") (pinfunction "14_14") (pintype "passive"))
      (node (ref "U$12") (pin "3") (pinfunction "3_3") (pintype "passive"))
    )
    (net (code "121") (name "Net-(B-OR-C-Pad40)") (class "Default")
      (node (ref "B-OR-C") (pin "40") (pinfunction "40_40") (pintype "bidirectional"))
      (node (ref "R12") (pin "4") (pinfunction "4_4") (pintype "passive"))
      (node (ref "S12") (pin "13") (pinfunction "13_13") (pintype "passive"))
      (node (ref "U$12") (pin "4") (pinfunction "4_4") (pintype "passive"))
    )
    (net (code "122") (name "Net-(B-OR-C-Pad41)") (class "Default")
      (node (ref "B-OR-C") (pin "41") (pinfunction "41_41") (pintype "bidirectional"))
      (node (ref "R12") (pin "5") (pinfunction "5_5") (pintype "passive"))
      (node (ref "S12") (pin "12") (pinfunction "12_12") (pintype "passive"))
      (node (ref "U$12") (pin "5") (pinfunction "5_5") (pintype "passive"))
    )
    (net (code "123") (name "Net-(B-OR-C-Pad42)") (class "Default")
      (node (ref "B-OR-C") (pin "42") (pinfunction "42_42") (pintype "bidirectional"))
      (node (ref "R12") (pin "6") (pinfunction "6_6") (pintype "passive"))
      (node (ref "S12") (pin "11") (pinfunction "11_11") (pintype "passive"))
      (node (ref "U$12") (pin "6") (pinfunction "6_6") (pintype "passive"))
    )
    (net (code "124") (name "Net-(B-OR-C-Pad43)") (class "Default")
      (node (ref "B-OR-C") (pin "43") (pinfunction "43_43") (pintype "bidirectional"))
      (node (ref "R12") (pin "7") (pinfunction "7_7") (pintype "passive"))
      (node (ref "S12") (pin "10") (pinfunction "10_10") (pintype "passive"))
      (node (ref "U$12") (pin "7") (pinfunction "7_7") (pintype "passive"))
    )
    (net (code "125") (name "Net-(B-OR-C-Pad44)") (class "Default")
      (node (ref "B-OR-C") (pin "44") (pinfunction "44_44") (pintype "bidirectional"))
      (node (ref "R12") (pin "8") (pinfunction "8_8") (pintype "passive"))
      (node (ref "S12") (pin "9") (pinfunction "9_9") (pintype "passive"))
      (node (ref "U$12") (pin "8") (pinfunction "8_8") (pintype "passive"))
    )
    (net (code "126") (name "Net-(B-OR-C-Pad45)") (class "Default")
      (node (ref "B-OR-C") (pin "45") (pinfunction "45_45") (pintype "bidirectional"))
      (node (ref "R11") (pin "1") (pinfunction "1_1") (pintype "passive"))
      (node (ref "S11") (pin "16") (pinfunction "16_16") (pintype "passive"))
      (node (ref "U$11") (pin "1") (pinfunction "1_1") (pintype "passive"))
    )
    (net (code "127") (name "Net-(B-OR-C-Pad46)") (class "Default")
      (node (ref "B-OR-C") (pin "46") (pinfunction "46_46") (pintype "bidirectional"))
      (node (ref "R11") (pin "2") (pinfunction "2_2") (pintype "passive"))
      (node (ref "S11") (pin "15") (pinfunction "15_15") (pintype "passive"))
      (node (ref "U$11") (pin "2") (pinfunction "2_2") (pintype "passive"))
    )
    (net (code "128") (name "Net-(B-OR-C-Pad47)") (class "Default")
      (node (ref "B-OR-C") (pin "47") (pinfunction "47_47") (pintype "bidirectional"))
      (node (ref "R11") (pin "3") (pinfunction "3_3") (pintype "passive"))
      (node (ref "S11") (pin "14") (pinfunction "14_14") (pintype "passive"))
      (node (ref "U$11") (pin "3") (pinfunction "3_3") (pintype "passive"))
    )
    (net (code "129") (name "Net-(B-OR-C-Pad48)") (class "Default")
      (node (ref "B-OR-C") (pin "48") (pinfunction "48_48") (pintype "bidirectional"))
      (node (ref "R11") (pin "4") (pinfunction "4_4") (pintype "passive"))
      (node (ref "S11") (pin "13") (pinfunction "13_13") (pintype "passive"))
      (node (ref "U$11") (pin "4") (pinfunction "4_4") (pintype "passive"))
    )
    (net (code "130") (name "Net-(B-OR-C-Pad49)") (class "Default")
      (node (ref "B-OR-C") (pin "49") (pinfunction "49_49") (pintype "bidirectional"))
      (node (ref "R11") (pin "5") (pinfunction "5_5") (pintype "passive"))
      (node (ref "S11") (pin "12") (pinfunction "12_12") (pintype "passive"))
      (node (ref "U$11") (pin "5") (pinfunction "5_5") (pintype "passive"))
    )
    (net (code "131") (name "Net-(B-OR-C-Pad50)") (class "Default")
      (node (ref "B-OR-C") (pin "50") (pinfunction "50_50") (pintype "bidirectional"))
      (node (ref "R11") (pin "6") (pinfunction "6_6") (pintype "passive"))
      (node (ref "S11") (pin "11") (pinfunction "11_11") (pintype "passive"))
      (node (ref "U$11") (pin "6") (pinfunction "6_6") (pintype "passive"))
    )
    (net (code "132") (name "Net-(B-OR-C-Pad51)") (class "Default")
      (node (ref "B-OR-C") (pin "51") (pinfunction "51_51") (pintype "bidirectional"))
      (node (ref "R11") (pin "7") (pinfunction "7_7") (pintype "passive"))
      (node (ref "S11") (pin "10") (pinfunction "10_10") (pintype "passive"))
      (node (ref "U$11") (pin "7") (pinfunction "7_7") (pintype "passive"))
    )
    (net (code "133") (name "Net-(B-OR-C-Pad52)") (class "Default")
      (node (ref "B-OR-C") (pin "52") (pinfunction "52_52") (pintype "bidirectional"))
      (node (ref "R11") (pin "8") (pinfunction "8_8") (pintype "passive"))
      (node (ref "S11") (pin "9") (pinfunction "9_9") (pintype "passive"))
      (node (ref "U$11") (pin "8") (pinfunction "8_8") (pintype "passive"))
    )
    (net (code "134") (name "Net-(B-OR-C-Pad53)") (class "Default")
      (node (ref "B-OR-C") (pin "53") (pinfunction "53_53") (pintype "bidirectional"))
      (node (ref "R10") (pin "1") (pinfunction "1_1") (pintype "passive"))
      (node (ref "S10") (pin "16") (pinfunction "16_16") (pintype "passive"))
      (node (ref "U$10") (pin "1") (pinfunction "1_1") (pintype "passive"))
    )
    (net (code "135") (name "Net-(B-OR-C-Pad54)") (class "Default")
      (node (ref "B-OR-C") (pin "54") (pinfunction "54_54") (pintype "bidirectional"))
      (node (ref "R10") (pin "2") (pinfunction "2_2") (pintype "passive"))
      (node (ref "S10") (pin "15") (pinfunction "15_15") (pintype "passive"))
      (node (ref "U$10") (pin "2") (pinfunction "2_2") (pintype "passive"))
    )
    (net (code "136") (name "Net-(B-OR-C-Pad55)") (class "Default")
      (node (ref "B-OR-C") (pin "55") (pinfunction "55_55") (pintype "bidirectional"))
      (node (ref "R10") (pin "3") (pinfunction "3_3") (pintype "passive"))
      (node (ref "S10") (pin "14") (pinfunction "14_14") (pintype "passive"))
      (node (ref "U$10") (pin "3") (pinfunction "3_3") (pintype "passive"))
    )
    (net (code "137") (name "Net-(B-OR-C-Pad56)") (class "Default")
      (node (ref "B-OR-C") (pin "56") (pinfunction "56_56") (pintype "bidirectional"))
      (node (ref "R10") (pin "4") (pinfunction "4_4") (pintype "passive"))
      (node (ref "S10") (pin "13") (pinfunction "13_13") (pintype "passive"))
      (node (ref "U$10") (pin "4") (pinfunction "4_4") (pintype "passive"))
    )
    (net (code "138") (name "Net-(B-OR-C-Pad57)") (class "Default")
      (node (ref "B-OR-C") (pin "57") (pinfunction "57_57") (pintype "bidirectional"))
      (node (ref "R10") (pin "5") (pinfunction "5_5") (pintype "passive"))
      (node (ref "S10") (pin "12") (pinfunction "12_12") (pintype "passive"))
      (node (ref "U$10") (pin "5") (pinfunction "5_5") (pintype "passive"))
    )
    (net (code "139") (name "Net-(B-OR-C-Pad58)") (class "Default")
      (node (ref "B-OR-C") (pin "58") (pinfunction "58_58") (pintype "bidirectional"))
      (node (ref "R10") (pin "6") (pinfunction "6_6") (pintype "passive"))
      (node (ref "S10") (pin "11") (pinfunction "11_11") (pintype "passive"))
      (node (ref "U$10") (pin "6") (pinfunction "6_6") (pintype "passive"))
    )
    (net (code "140") (name "Net-(B-OR-C-Pad59)") (class "Default")
      (node (ref "B-OR-C") (pin "59") (pinfunction "59_59") (pintype "bidirectional"))
      (node (ref "R10") (pin "7") (pinfunction "7_7") (pintype "passive"))
      (node (ref "S10") (pin "10") (pinfunction "10_10") (pintype "passive"))
      (node (ref "U$10") (pin "7") (pinfunction "7_7") (pintype "passive"))
    )
    (net (code "141") (name "Net-(B-OR-C-Pad60)") (class "Default")
      (node (ref "B-OR-C") (pin "60") (pinfunction "60_60") (pintype "bidirectional"))
      (node (ref "R10") (pin "8") (pinfunction "8_8") (pintype "passive"))
      (node (ref "S10") (pin "9") (pinfunction "9_9") (pintype "passive"))
      (node (ref "U$10") (pin "8") (pinfunction "8_8") (pintype "passive"))
    )
    (net (code "142") (name "Net-(B-OR-C-Pad61)") (class "Default")
      (node (ref "B-OR-C") (pin "61") (pinfunction "61_61") (pintype "bidirectional"))
      (node (ref "R9") (pin "1") (pinfunction "1_1") (pintype "passive"))
      (node (ref "S9") (pin "16") (pinfunction "16_16") (pintype "passive"))
      (node (ref "U$9") (pin "1") (pinfunction "1_1") (pintype "passive"))
    )
    (net (code "143") (name "Net-(B-OR-C-Pad62)") (class "Default")
      (node (ref "B-OR-C") (pin "62") (pinfunction "62_62") (pintype "bidirectional"))
      (node (ref "R9") (pin "2") (pinfunction "2_2") (pintype "passive"))
      (node (ref "S9") (pin "15") (pinfunction "15_15") (pintype "passive"))
      (node (ref "U$9") (pin "2") (pinfunction "2_2") (pintype "passive"))
    )
    (net (code "144") (name "Net-(B-OR-C-Pad63)") (class "Default")
      (node (ref "B-OR-C") (pin "63") (pinfunction "63_63") (pintype "bidirectional"))
      (node (ref "R9") (pin "3") (pinfunction "3_3") (pintype "passive"))
      (node (ref "S9") (pin "14") (pinfunction "14_14") (pintype "passive"))
      (node (ref "U$9") (pin "3") (pinfunction "3_3") (pintype "passive"))
    )
    (net (code "145") (name "Net-(B-OR-C-Pad64)") (class "Default")
      (node (ref "B-OR-C") (pin "64") (pinfunction "64_64") (pintype "bidirectional"))
      (node (ref "R9") (pin "4") (pinfunction "4_4") (pintype "passive"))
      (node (ref "S9") (pin "13") (pinfunction "13_13") (pintype "passive"))
      (node (ref "U$9") (pin "4") (pinfunction "4_4") (pintype "passive"))
    )
    (net (code "146") (name "Net-(B-OR-C-Pad65)") (class "Default")
      (node (ref "B-OR-C") (pin "65") (pinfunction "65_65") (pintype "bidirectional"))
      (node (ref "R9") (pin "5") (pinfunction "5_5") (pintype "passive"))
      (node (ref "S9") (pin "12") (pinfunction "12_12") (pintype "passive"))
      (node (ref "U$9") (pin "5") (pinfunction "5_5") (pintype "passive"))
    )
    (net (code "147") (name "Net-(B-OR-C-Pad66)") (class "Default")
      (node (ref "B-OR-C") (pin "66") (pinfunction "66_66") (pintype "bidirectional"))
      (node (ref "R9") (pin "6") (pinfunction "6_6") (pintype "passive"))
      (node (ref "S9") (pin "11") (pinfunction "11_11") (pintype "passive"))
      (node (ref "U$9") (pin "6") (pinfunction "6_6") (pintype "passive"))
    )
    (net (code "148") (name "Net-(B-OR-C-Pad67)") (class "Default")
      (node (ref "B-OR-C") (pin "67") (pinfunction "67_67") (pintype "bidirectional"))
      (node (ref "R9") (pin "7") (pinfunction "7_7") (pintype "passive"))
      (node (ref "S9") (pin "10") (pinfunction "10_10") (pintype "passive"))
      (node (ref "U$9") (pin "7") (pinfunction "7_7") (pintype "passive"))
    )
    (net (code "149") (name "Net-(B-OR-C-Pad68)") (class "Default")
      (node (ref "B-OR-C") (pin "68") (pinfunction "68_68") (pintype "bidirectional"))
      (node (ref "R9") (pin "8") (pinfunction "8_8") (pintype "passive"))
      (node (ref "S9") (pin "9") (pinfunction "9_9") (pintype "passive"))
      (node (ref "U$9") (pin "8") (pinfunction "8_8") (pintype "passive"))
    )
    (net (code "150") (name "Net-(CDL_A-Pad1)") (class "Default")
      (node (ref "CDL_A") (pin "1") (pinfunction "1_1") (pintype "passive"))
      (node (ref "RS_A") (pin "2") (pinfunction "2_2") (pintype "passive"))
    )
    (net (code "151") (name "Net-(CDL_B-Pad1)") (class "Default")
      (node (ref "CDL_B") (pin "1") (pinfunction "1_1") (pintype "passive"))
      (node (ref "RS_B") (pin "2") (pinfunction "2_2") (pintype "passive"))
    )
    (net (code "152") (name "Net-(D1-PadA)") (class "Default")
      (node (ref "D1") (pin "A") (pinfunction "A_A") (pintype "passive"))
      (node (ref "D2") (pin "A") (pinfunction "A_A") (pintype "passive"))
      (node (ref "LED_SELECT_A") (pin "3") (pinfunction "3_3") (pintype "passive"))
    )
    (net (code "153") (name "Net-(D1_EXT_A-Pad2)") (class "Default")
      (node (ref "D1_EXT_A") (pin "2") (pinfunction "2_2") (pintype "passive"))
      (node (ref "D2_EXT_A") (pin "2") (pinfunction "2_2") (pintype "passive"))
      (node (ref "LED_SELECT_A") (pin "1") (pinfunction "1_1") (pintype "passive"))
    )
    (net (code "154") (name "Net-(D1_EXT_B-Pad2)") (class "Default")
      (node (ref "D1_EXT_B") (pin "2") (pinfunction "2_2") (pintype "passive"))
      (node (ref "D2_EXT_B") (pin "2") (pinfunction "2_2") (pintype "passive"))
      (node (ref "LED_SELECT_B") (pin "1") (pinfunction "1_1") (pintype "passive"))
    )
    (net (code "155") (name "Net-(D3-PadA)") (class "Default")
      (node (ref "D3") (pin "A") (pinfunction "A_A") (pintype "passive"))
      (node (ref "D4") (pin "A") (pinfunction "A_A") (pintype "passive"))
      (node (ref "LED_SELECT_B") (pin "3") (pinfunction "3_3") (pintype "passive"))
    )
    (net (code "156") (name "Net-(GND_IMP-Pad3)") (class "Default")
      (node (ref "GND_IMP") (pin "3") (pinfunction "3_3") (pintype "passive"))
      (node (ref "R_GND") (pin "1") (pinfunction "1_1") (pintype "passive"))
    )
    (net (code "157") (name "Net-(REF_TO_GND-Pad3)") (class "Default")
      (node (ref "REF_TO_GND") (pin "3") (pinfunction "3_3") (pintype "passive"))
      (node (ref "R_REF") (pin "1") (pinfunction "1_1") (pintype "passive"))
    )
    (net (code "158") (name "REF") (class "Default")
      (node (ref "A-OR-D") (pin "1") (pinfunction "1_1") (pintype "bidirectional"))
      (node (ref "B-OR-C") (pin "1") (pinfunction "1_1") (pintype "bidirectional"))
      (node (ref "REF_TO_GND") (pin "2") (pinfunction "2_2") (pintype "passive"))
      (node (ref "RS_A") (pin "1") (pinfunction "1_1") (pintype "passive"))
      (node (ref "RS_B") (pin "1") (pinfunction "1_1") (pintype "passive"))
    )
    (net (code "159") (name "SIG_IN") (class "Default")
      (node (ref "R17") (pin "1") (pinfunction "1_1") (pintype "passive"))
      (node (ref "SIG_IN") (pin "P$SIG") (pinfunction "SIG_P$SIG") (pintype "bidirectional"))
      (node (ref "TP7") (pin "TP") (pinfunction "TP_TP") (pintype "input"))
    )
    (net (code "160") (name "unconnected-(A-OR-D-PadM1)") (class "Default")
      (node (ref "A-OR-D") (pin "M1") (pinfunction "M1_M1") (pintype "bidirectional"))
    )
    (net (code "161") (name "unconnected-(A-OR-D-PadM2)") (class "Default")
      (node (ref "A-OR-D") (pin "M2") (pinfunction "M2_M2") (pintype "bidirectional"))
    )
    (net (code "162") (name "unconnected-(A-OR-D-PadM3)") (class "Default")
      (node (ref "A-OR-D") (pin "M3") (pinfunction "M3_M3") (pintype "bidirectional"))
    )
    (net (code "163") (name "unconnected-(A-OR-D-PadM4)") (class "Default")
      (node (ref "A-OR-D") (pin "M4") (pinfunction "M4_M4") (pintype "bidirectional"))
    )
    (net (code "164") (name "unconnected-(B-OR-C-PadM1)") (class "Default")
      (node (ref "B-OR-C") (pin "M1") (pinfunction "M1_M1") (pintype "bidirectional"))
    )
    (net (code "165") (name "unconnected-(B-OR-C-PadM2)") (class "Default")
      (node (ref "B-OR-C") (pin "M2") (pinfunction "M2_M2") (pintype "bidirectional"))
    )
    (net (code "166") (name "unconnected-(B-OR-C-PadM3)") (class "Default")
      (node (ref "B-OR-C") (pin "M3") (pinfunction "M3_M3") (pintype "bidirectional"))
    )
    (net (code "167") (name "unconnected-(B-OR-C-PadM4)") (class "Default")
      (node (ref "B-OR-C") (pin "M4") (pinfunction "M4_M4") (pintype "bidirectional"))
    )
  )
)
